# Motherboard_-_Rev2.net
KiCad netlist of a schematic drawn in EAGLE
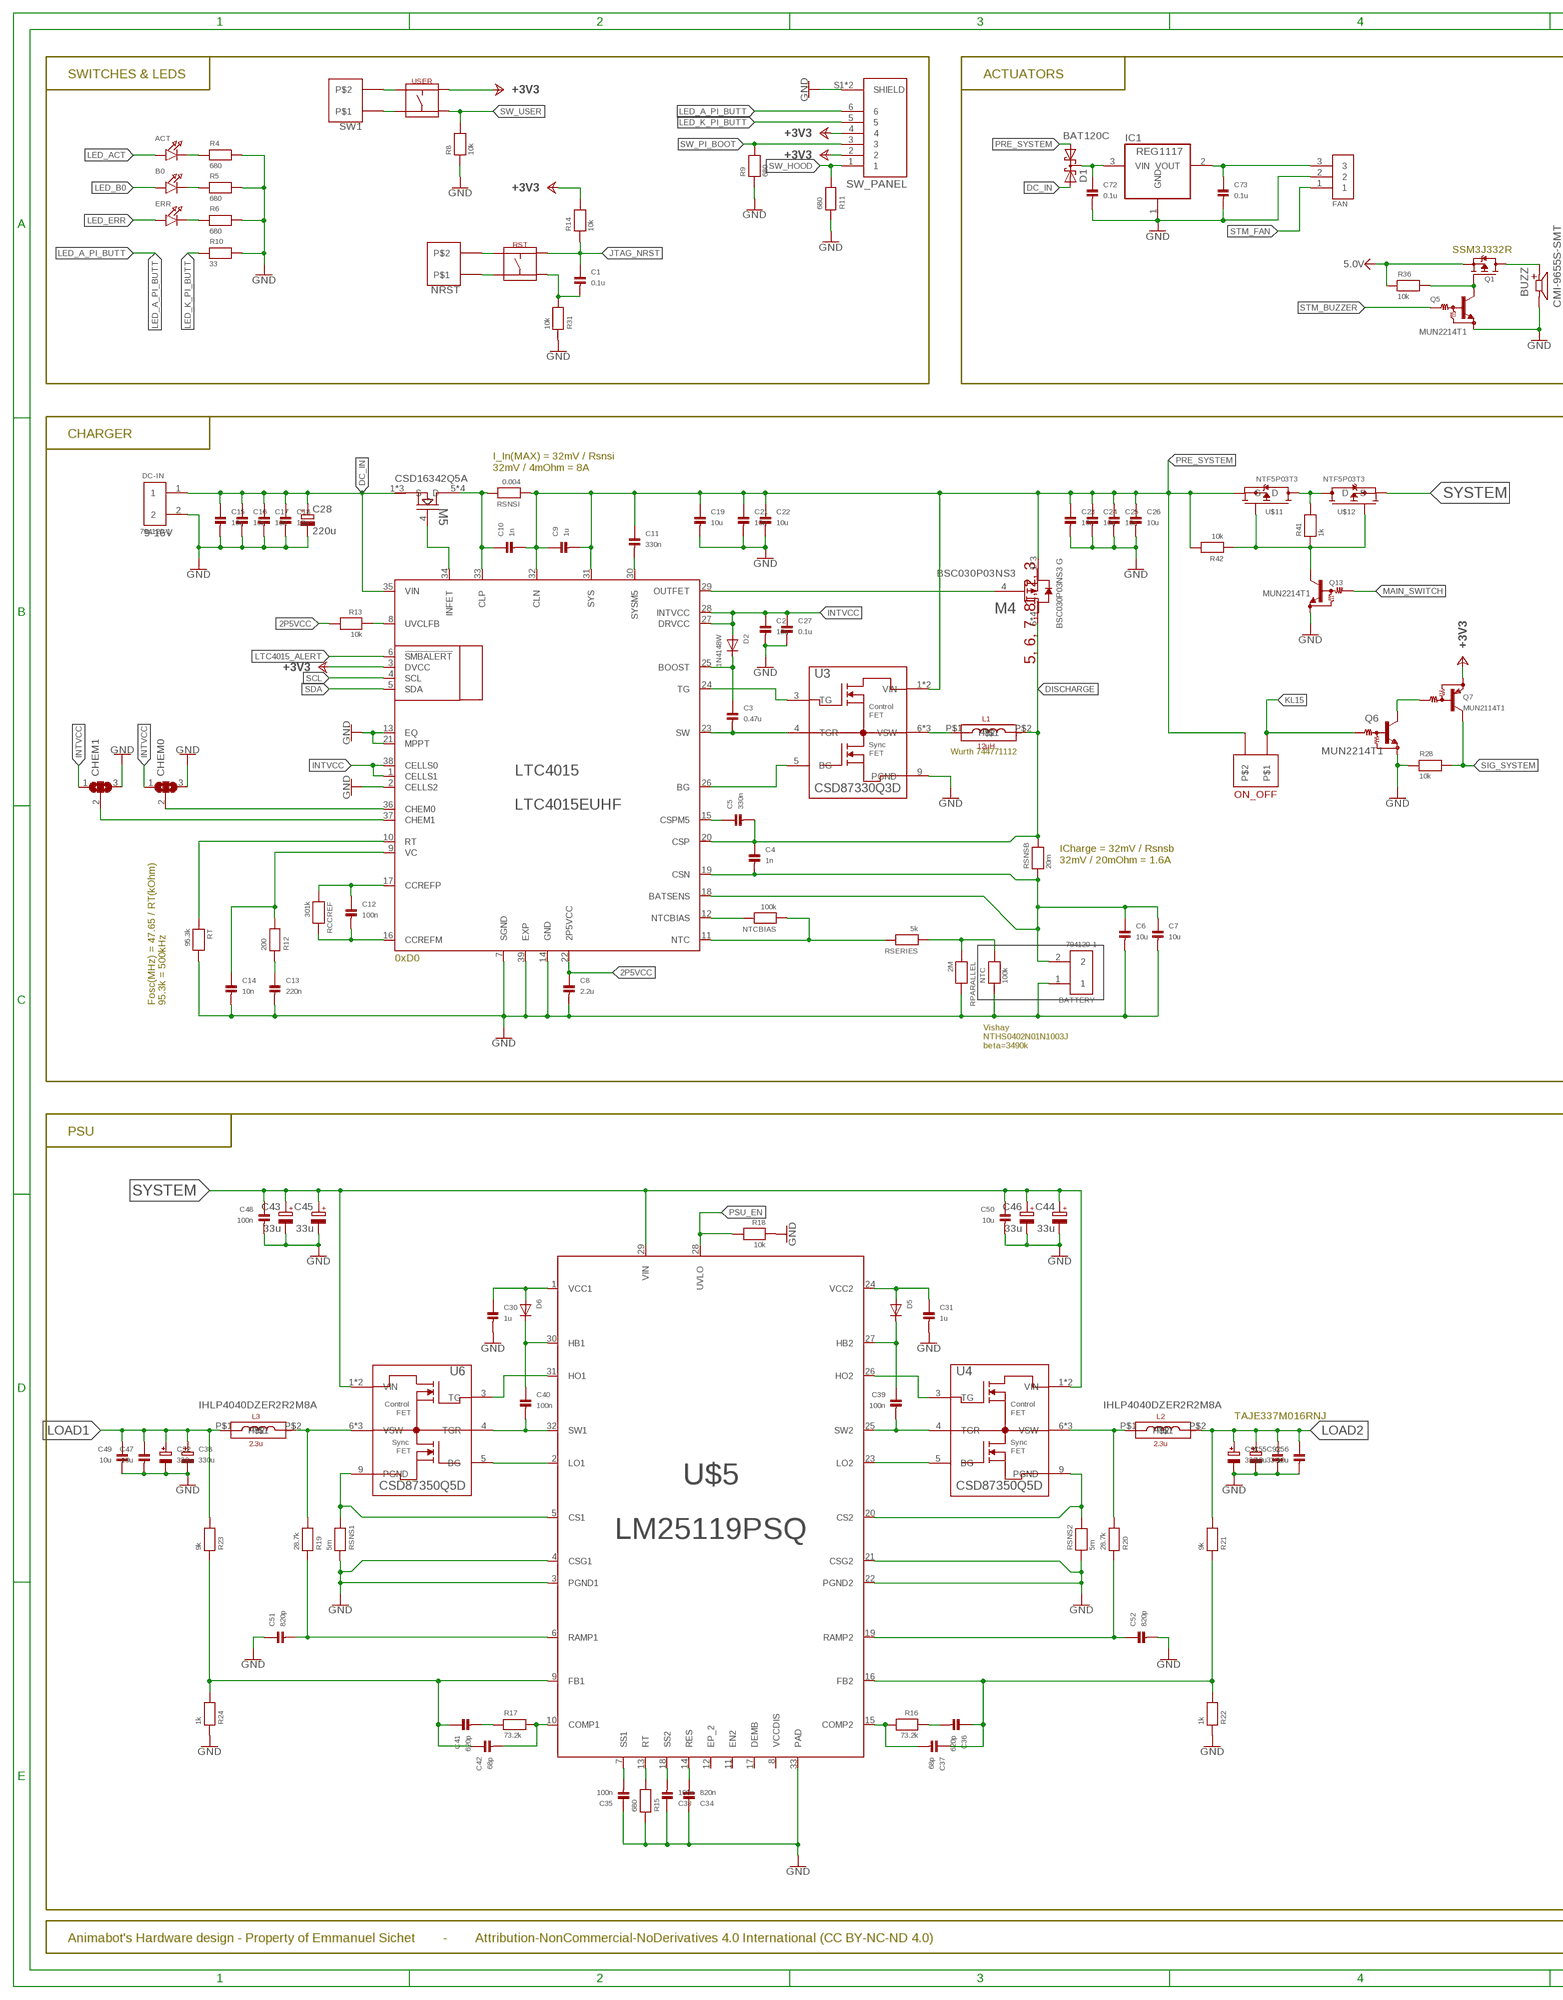
[diagram p0: schematic, sheet 1, part 1 of 2]
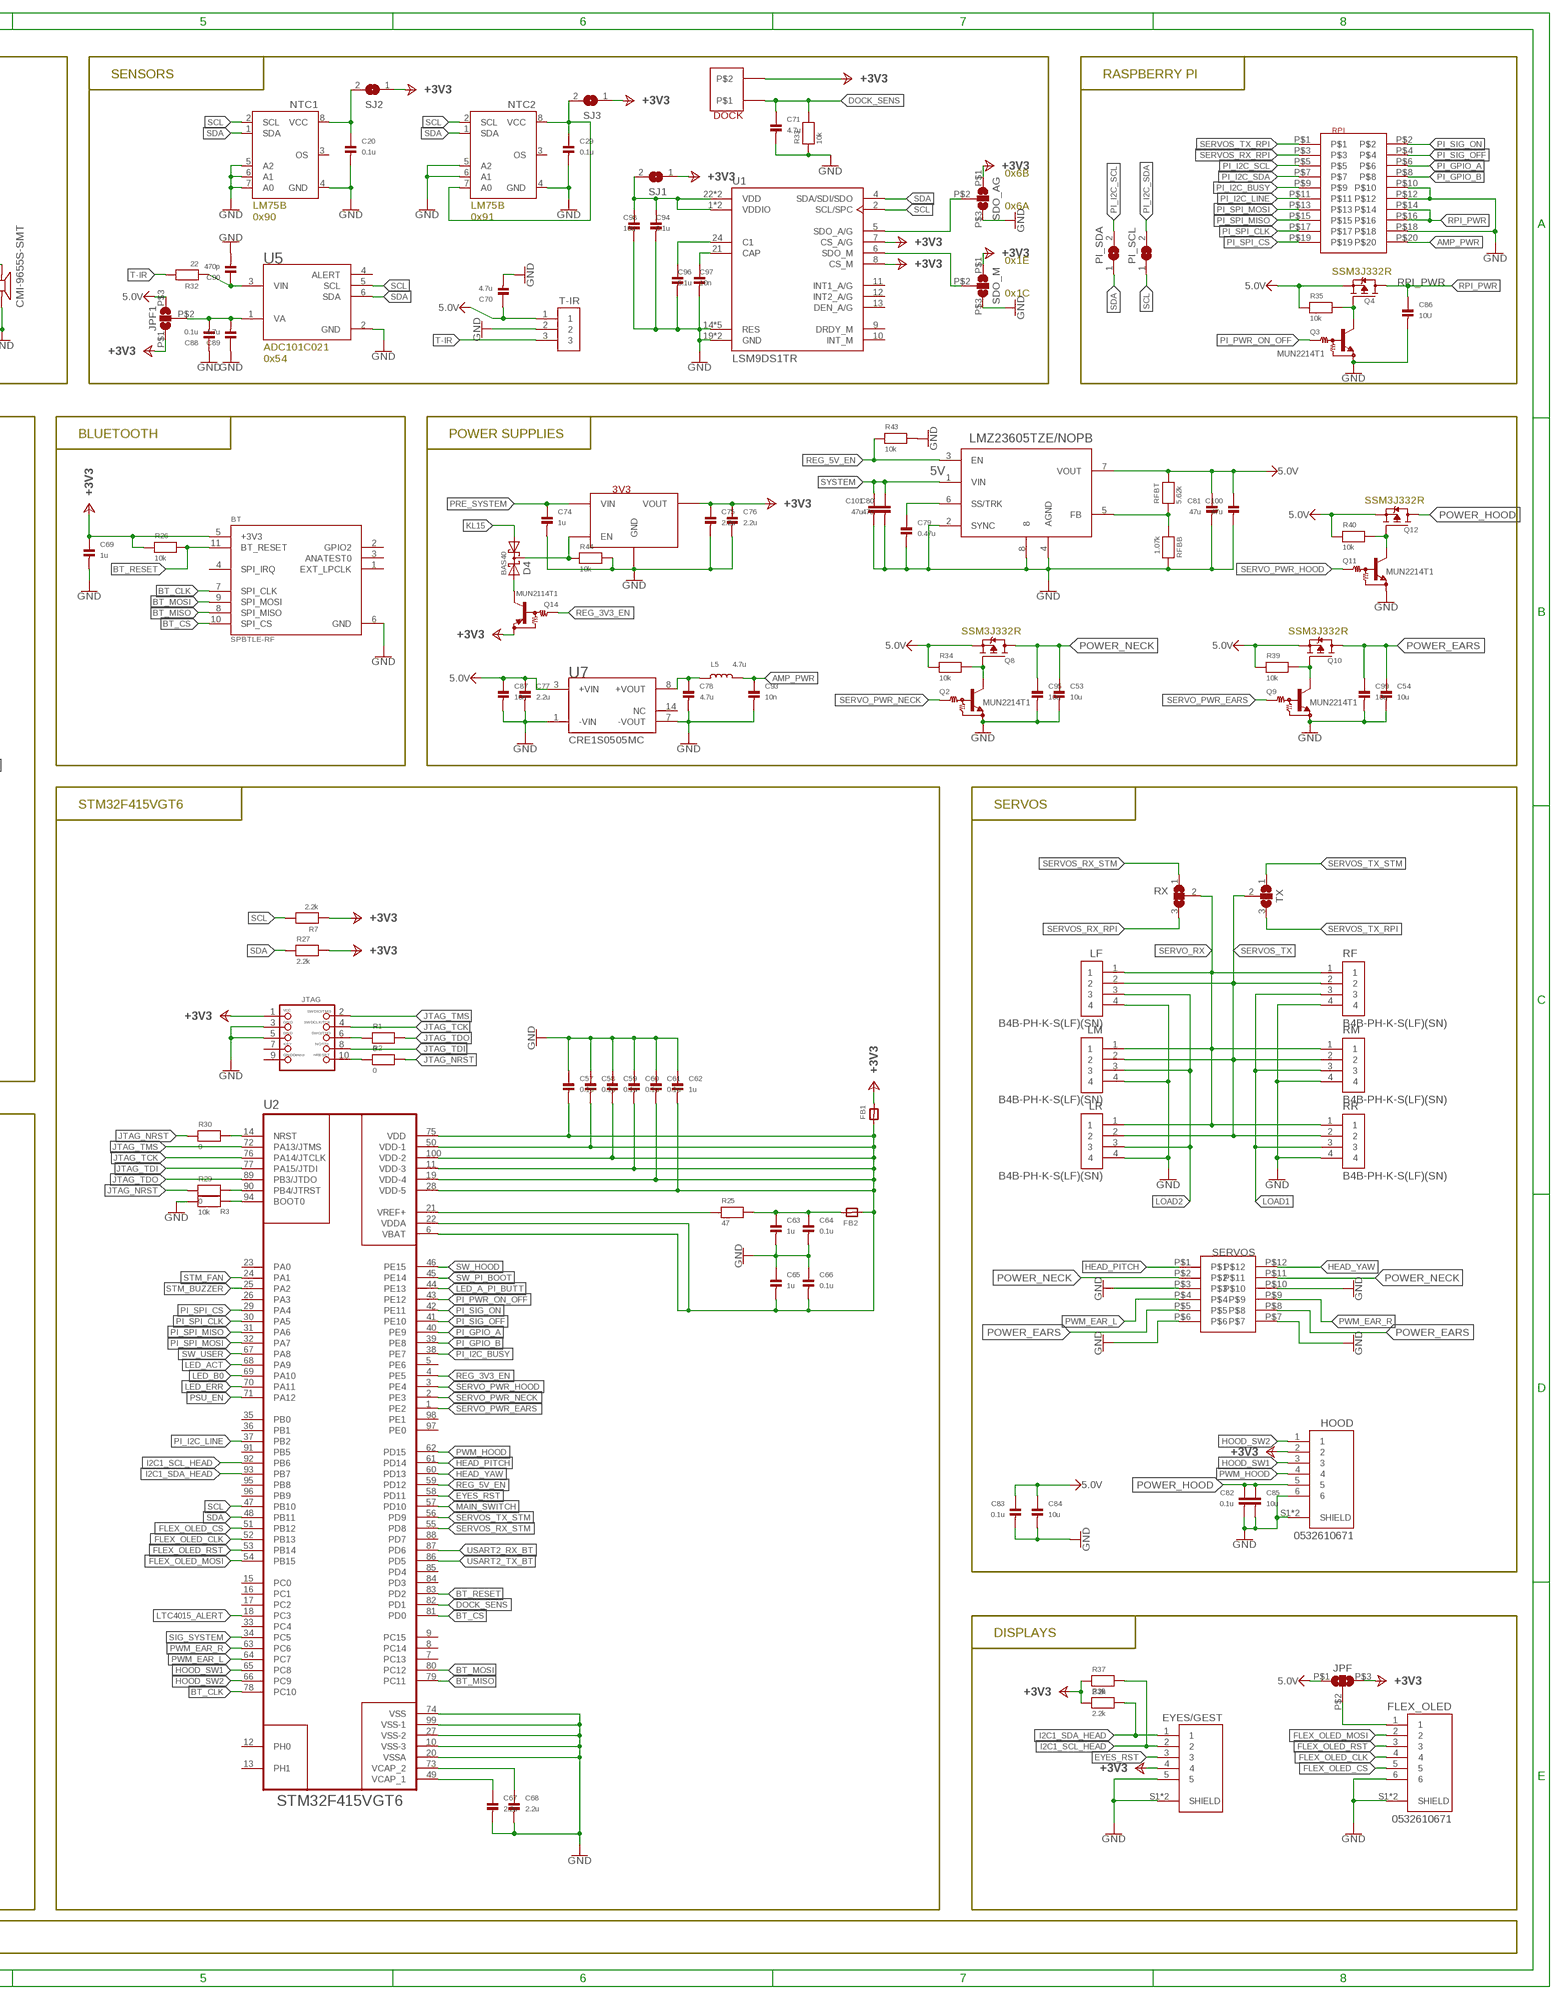
[diagram p1: schematic, sheet 1, part 2 of 2]

(export (version "E")
  (design (tool "Eeschema 10.0.6"))
  (components
    (comp (ref "3V3")
      (value "NCP5500DT-33.50-RKG")
      (footprint "eagle-import:NCP5500DT-33.50-RKG")
      (libsource (lib "eagle-import") (part "NCP5500DT-33.50-RKG"))
    )
    (comp (ref "5V")
      (value "LMZ23605TZE/NOPB")
      (footprint "eagle-import:TZA07A")
      (fields (field (name "MANUFACTURER_PART_NUMBER") "LMZ23605TZENOPB"))
      (libsource (lib "eagle-import") (part "LMZ23605TZE/NOPB"))
    )
    (comp (ref "ACT")
      (value "LED0805")
      (footprint "eagle-import:CHIPLED_0805")
      (libsource (lib "eagle-import") (part "LED0805"))
    )
    (comp (ref "B0")
      (value "LED0805")
      (footprint "eagle-import:CHIPLED_0805")
      (libsource (lib "eagle-import") (part "LED0805"))
    )
    (comp (ref "BATTERY")
      (value "794120-1")
      (footprint "eagle-import:TE_794120-1")
      (fields (field (name "MF") "TE Connectivity"))
      (libsource (lib "eagle-import") (part "794120-1"))
    )
    (comp (ref "BT")
      (value "SPBTLE-RF")
      (footprint "eagle-import:XCVR_SPBTLE-RF")
      (fields (field (name "MF") "STMicroelectronics"))
      (libsource (lib "eagle-import") (part "SPBTLE-RF"))
    )
    (comp (ref "BUZZ")
      (value "CMI-9655S-SMT")
      (footprint "eagle-import:CUI_CMI-9655S-SMT")
      (fields (field (name "MANUFACTURER") "CUI INC"))
      (libsource (lib "eagle-import") (part "CMI-9655S-SMT"))
    )
    (comp (ref "C1")
      (value "0.1u")
      (footprint "eagle-import:0805")
      (libsource (lib "eagle-import") (part "CAP_CERAMIC0805"))
    )
    (comp (ref "C2")
      (value "10u")
      (footprint "eagle-import:0805")
      (libsource (lib "eagle-import") (part "CAP_CERAMIC0805"))
    )
    (comp (ref "C3")
      (value "0.47u")
      (footprint "eagle-import:0805")
      (libsource (lib "eagle-import") (part "CAP_CERAMIC0805"))
    )
    (comp (ref "C4")
      (value "1n")
      (footprint "eagle-import:0805")
      (libsource (lib "eagle-import") (part "CAP_CERAMIC0805"))
    )
    (comp (ref "C5")
      (value "330n")
      (footprint "eagle-import:0805")
      (libsource (lib "eagle-import") (part "CAP_CERAMIC0805"))
    )
    (comp (ref "C6")
      (value "10u")
      (footprint "eagle-import:1206")
      (libsource (lib "eagle-import") (part "CAP_CERAMIC1206"))
    )
    (comp (ref "C7")
      (value "10u")
      (footprint "eagle-import:1206")
      (libsource (lib "eagle-import") (part "CAP_CERAMIC1206"))
    )
    (comp (ref "C8")
      (value "2.2u")
      (footprint "eagle-import:0805")
      (libsource (lib "eagle-import") (part "CAP_CERAMIC0805"))
    )
    (comp (ref "C9")
      (value "1u")
      (footprint "eagle-import:0805")
      (libsource (lib "eagle-import") (part "CAP_CERAMIC0805"))
    )
    (comp (ref "C10")
      (value "1n")
      (footprint "eagle-import:0805")
      (libsource (lib "eagle-import") (part "CAP_CERAMIC0805"))
    )
    (comp (ref "C11")
      (value "330n")
      (footprint "eagle-import:0805")
      (libsource (lib "eagle-import") (part "CAP_CERAMIC0805"))
    )
    (comp (ref "C12")
      (value "100n")
      (footprint "eagle-import:0805")
      (libsource (lib "eagle-import") (part "CAP_CERAMIC0805"))
    )
    (comp (ref "C13")
      (value "220n")
      (footprint "eagle-import:0805")
      (libsource (lib "eagle-import") (part "CAP_CERAMIC0805"))
    )
    (comp (ref "C14")
      (value "10n")
      (footprint "eagle-import:0805")
      (libsource (lib "eagle-import") (part "CAP_CERAMIC0805"))
    )
    (comp (ref "C15")
      (value "10u")
      (footprint "eagle-import:1206")
      (libsource (lib "eagle-import") (part "CAP_CERAMIC1206"))
    )
    (comp (ref "C16")
      (value "10u")
      (footprint "eagle-import:1206")
      (libsource (lib "eagle-import") (part "CAP_CERAMIC1206"))
    )
    (comp (ref "C17")
      (value "10u")
      (footprint "eagle-import:1206")
      (libsource (lib "eagle-import") (part "CAP_CERAMIC1206"))
    )
    (comp (ref "C18")
      (value "10u")
      (footprint "eagle-import:1206")
      (libsource (lib "eagle-import") (part "CAP_CERAMIC1206"))
    )
    (comp (ref "C19")
      (value "10u")
      (footprint "eagle-import:1206")
      (libsource (lib "eagle-import") (part "CAP_CERAMIC1206"))
    )
    (comp (ref "C20")
      (value "0.1u")
      (footprint "eagle-import:0805")
      (libsource (lib "eagle-import") (part "CAP_CERAMIC0805"))
    )
    (comp (ref "C21")
      (value "10u")
      (footprint "eagle-import:1206")
      (libsource (lib "eagle-import") (part "CAP_CERAMIC1206"))
    )
    (comp (ref "C22")
      (value "10u")
      (footprint "eagle-import:1206")
      (libsource (lib "eagle-import") (part "CAP_CERAMIC1206"))
    )
    (comp (ref "C23")
      (value "10u")
      (footprint "eagle-import:1206")
      (libsource (lib "eagle-import") (part "CAP_CERAMIC1206"))
    )
    (comp (ref "C24")
      (value "10u")
      (footprint "eagle-import:1206")
      (libsource (lib "eagle-import") (part "CAP_CERAMIC1206"))
    )
    (comp (ref "C25")
      (value "10u")
      (footprint "eagle-import:1206")
      (libsource (lib "eagle-import") (part "CAP_CERAMIC1206"))
    )
    (comp (ref "C26")
      (value "10u")
      (footprint "eagle-import:1206")
      (libsource (lib "eagle-import") (part "CAP_CERAMIC1206"))
    )
    (comp (ref "C27")
      (value "0.1u")
      (footprint "eagle-import:0805")
      (libsource (lib "eagle-import") (part "CAP_CERAMIC0805"))
    )
    (comp (ref "C28")
      (value "220u")
      (footprint "eagle-import:UD-10X10_NICHICON")
      (libsource (lib "eagle-import") (part "CPOL-EUUD-10X10"))
    )
    (comp (ref "C29")
      (value "0.1u")
      (footprint "eagle-import:0805")
      (libsource (lib "eagle-import") (part "CAP_CERAMIC0805"))
    )
    (comp (ref "C30")
      (value "1u")
      (footprint "eagle-import:0805")
      (libsource (lib "eagle-import") (part "CAP_CERAMIC0805"))
    )
    (comp (ref "C31")
      (value "1u")
      (footprint "eagle-import:0805")
      (libsource (lib "eagle-import") (part "CAP_CERAMIC0805"))
    )
    (comp (ref "C32")
      (value "330u")
      (footprint "eagle-import:EIA7343-31_D-R")
      (libsource (lib "eagle-import") (part "CAP_TANTALUMD/7343_REFLOW"))
    )
    (comp (ref "C33")
      (value "100n")
      (footprint "eagle-import:0805")
      (libsource (lib "eagle-import") (part "CAP_CERAMIC0805"))
    )
    (comp (ref "C34")
      (value "820n")
      (footprint "eagle-import:0805")
      (libsource (lib "eagle-import") (part "CAP_CERAMIC0805"))
    )
    (comp (ref "C35")
      (value "100n")
      (footprint "eagle-import:0805")
      (libsource (lib "eagle-import") (part "CAP_CERAMIC0805"))
    )
    (comp (ref "C36")
      (value "620p")
      (footprint "eagle-import:0805")
      (libsource (lib "eagle-import") (part "CAP_CERAMIC0805"))
    )
    (comp (ref "C37")
      (value "68p")
      (footprint "eagle-import:0805")
      (libsource (lib "eagle-import") (part "CAP_CERAMIC0805"))
    )
    (comp (ref "C38")
      (value "330u")
      (footprint "eagle-import:EIA7343-31_D-R")
      (libsource (lib "eagle-import") (part "CAP_TANTALUMD/7343_REFLOW"))
    )
    (comp (ref "C39")
      (value "100n")
      (footprint "eagle-import:0805")
      (libsource (lib "eagle-import") (part "CAP_CERAMIC0805"))
    )
    (comp (ref "C40")
      (value "100n")
      (footprint "eagle-import:0805")
      (libsource (lib "eagle-import") (part "CAP_CERAMIC0805"))
    )
    (comp (ref "C41")
      (value "620p")
      (footprint "eagle-import:0805")
      (libsource (lib "eagle-import") (part "CAP_CERAMIC0805"))
    )
    (comp (ref "C42")
      (value "68p")
      (footprint "eagle-import:0805")
      (libsource (lib "eagle-import") (part "CAP_CERAMIC0805"))
    )
    (comp (ref "C43")
      (value "33u")
      (footprint "eagle-import:UD-6,3X7,7_NICHICON")
      (libsource (lib "eagle-import") (part "CPOL-EUUD-6,3X7,7"))
    )
    (comp (ref "C44")
      (value "33u")
      (footprint "eagle-import:UD-6,3X7,7_NICHICON")
      (libsource (lib "eagle-import") (part "CPOL-EUUD-6,3X7,7"))
    )
    (comp (ref "C45")
      (value "33u")
      (footprint "eagle-import:UD-6,3X7,7_NICHICON")
      (libsource (lib "eagle-import") (part "CPOL-EUUD-6,3X7,7"))
    )
    (comp (ref "C46")
      (value "33u")
      (footprint "eagle-import:UD-6,3X7,7_NICHICON")
      (libsource (lib "eagle-import") (part "CPOL-EUUD-6,3X7,7"))
    )
    (comp (ref "C47")
      (value "10u")
      (footprint "eagle-import:1206")
      (libsource (lib "eagle-import") (part "CAP_CERAMIC1206"))
    )
    (comp (ref "C48")
      (value "100n")
      (footprint "eagle-import:1206")
      (libsource (lib "eagle-import") (part "CAP_CERAMIC1206"))
    )
    (comp (ref "C49")
      (value "10u")
      (footprint "eagle-import:1206")
      (libsource (lib "eagle-import") (part "CAP_CERAMIC1206"))
    )
    (comp (ref "C50")
      (value "10u")
      (footprint "eagle-import:1206")
      (libsource (lib "eagle-import") (part "CAP_CERAMIC1206"))
    )
    (comp (ref "C51")
      (value "820p")
      (footprint "eagle-import:0805")
      (libsource (lib "eagle-import") (part "CAP_CERAMIC0805"))
    )
    (comp (ref "C52")
      (value "820p")
      (footprint "eagle-import:0805")
      (libsource (lib "eagle-import") (part "CAP_CERAMIC0805"))
    )
    (comp (ref "C53")
      (value "10u")
      (footprint "eagle-import:1206")
      (libsource (lib "eagle-import") (part "CAP_CERAMIC1206"))
    )
    (comp (ref "C54")
      (value "10u")
      (footprint "eagle-import:1206")
      (libsource (lib "eagle-import") (part "CAP_CERAMIC1206"))
    )
    (comp (ref "C55")
      (value "10u")
      (footprint "eagle-import:1206")
      (libsource (lib "eagle-import") (part "CAP_CERAMIC1206"))
    )
    (comp (ref "C56")
      (value "10u")
      (footprint "eagle-import:1206")
      (libsource (lib "eagle-import") (part "CAP_CERAMIC1206"))
    )
    (comp (ref "C57")
      (value "0.1u")
      (footprint "eagle-import:0805")
      (libsource (lib "eagle-import") (part "CAP_CERAMIC0805"))
    )
    (comp (ref "C58")
      (value "0.1u")
      (footprint "eagle-import:0805")
      (libsource (lib "eagle-import") (part "CAP_CERAMIC0805"))
    )
    (comp (ref "C59")
      (value "0.1u")
      (footprint "eagle-import:0805")
      (libsource (lib "eagle-import") (part "CAP_CERAMIC0805"))
    )
    (comp (ref "C60")
      (value "0.1u")
      (footprint "eagle-import:0805")
      (libsource (lib "eagle-import") (part "CAP_CERAMIC0805"))
    )
    (comp (ref "C61")
      (value "0.1u")
      (footprint "eagle-import:0805")
      (libsource (lib "eagle-import") (part "CAP_CERAMIC0805"))
    )
    (comp (ref "C62")
      (value "1u")
      (footprint "eagle-import:0805")
      (libsource (lib "eagle-import") (part "CAP_CERAMIC0805"))
    )
    (comp (ref "C63")
      (value "1u")
      (footprint "eagle-import:0805")
      (libsource (lib "eagle-import") (part "CAP_CERAMIC0805"))
    )
    (comp (ref "C64")
      (value "0.1u")
      (footprint "eagle-import:0805")
      (libsource (lib "eagle-import") (part "CAP_CERAMIC0805"))
    )
    (comp (ref "C65")
      (value "1u")
      (footprint "eagle-import:0805")
      (libsource (lib "eagle-import") (part "CAP_CERAMIC0805"))
    )
    (comp (ref "C66")
      (value "0.1u")
      (footprint "eagle-import:0805")
      (libsource (lib "eagle-import") (part "CAP_CERAMIC0805"))
    )
    (comp (ref "C67")
      (value "2.2u")
      (footprint "eagle-import:0805")
      (libsource (lib "eagle-import") (part "CAP_CERAMIC0805"))
    )
    (comp (ref "C68")
      (value "2.2u")
      (footprint "eagle-import:0805")
      (libsource (lib "eagle-import") (part "CAP_CERAMIC0805"))
    )
    (comp (ref "C69")
      (value "1u")
      (footprint "eagle-import:0805")
      (libsource (lib "eagle-import") (part "CAP_CERAMIC0805"))
    )
    (comp (ref "C70")
      (value "4.7u")
      (footprint "eagle-import:0805")
      (libsource (lib "eagle-import") (part "CAP_CERAMIC0805"))
    )
    (comp (ref "C71")
      (value "4.7u")
      (footprint "eagle-import:0805")
      (libsource (lib "eagle-import") (part "CAP_CERAMIC0805"))
    )
    (comp (ref "C72")
      (value "0.1u")
      (footprint "eagle-import:0805")
      (libsource (lib "eagle-import") (part "CAP_CERAMIC0805"))
    )
    (comp (ref "C73")
      (value "0.1u")
      (footprint "eagle-import:0805")
      (libsource (lib "eagle-import") (part "CAP_CERAMIC0805"))
    )
    (comp (ref "C74")
      (value "1u")
      (footprint "eagle-import:0805")
      (libsource (lib "eagle-import") (part "CAP_CERAMIC0805"))
    )
    (comp (ref "C75")
      (value "2.2u")
      (footprint "eagle-import:0805")
      (libsource (lib "eagle-import") (part "CAP_CERAMIC0805"))
    )
    (comp (ref "C76")
      (value "2.2u")
      (footprint "eagle-import:0805")
      (libsource (lib "eagle-import") (part "CAP_CERAMIC0805"))
    )
    (comp (ref "C77")
      (value "2.2u")
      (footprint "eagle-import:0805")
      (libsource (lib "eagle-import") (part "CAP_CERAMIC0805"))
    )
    (comp (ref "C78")
      (value "4.7u")
      (footprint "eagle-import:0805")
      (libsource (lib "eagle-import") (part "CAP_CERAMIC0805"))
    )
    (comp (ref "C79")
      (value "0.47u")
      (footprint "eagle-import:0805")
      (libsource (lib "eagle-import") (part "CAP_CERAMIC0805"))
    )
    (comp (ref "C80")
      (value "47u")
      (footprint "eagle-import:1206")
      (libsource (lib "eagle-import") (part "CAP_CERAMIC1206"))
    )
    (comp (ref "C81")
      (value "47u")
      (footprint "eagle-import:1206")
      (libsource (lib "eagle-import") (part "CAP_CERAMIC1206"))
    )
    (comp (ref "C82")
      (value "0.1u")
      (footprint "eagle-import:0805")
      (libsource (lib "eagle-import") (part "CAP_CERAMIC0805"))
    )
    (comp (ref "C83")
      (value "0.1u")
      (footprint "eagle-import:0805")
      (libsource (lib "eagle-import") (part "CAP_CERAMIC0805"))
    )
    (comp (ref "C84")
      (value "10u")
      (footprint "eagle-import:1206")
      (libsource (lib "eagle-import") (part "CAP_CERAMIC1206"))
    )
    (comp (ref "C85")
      (value "10u")
      (footprint "eagle-import:1206")
      (libsource (lib "eagle-import") (part "CAP_CERAMIC1206"))
    )
    (comp (ref "C86")
      (value "10U")
      (footprint "eagle-import:0805")
      (libsource (lib "eagle-import") (part "CAP_CERAMIC0805"))
    )
    (comp (ref "C87")
      (value "10n")
      (footprint "eagle-import:0805")
      (libsource (lib "eagle-import") (part "CAP_CERAMIC0805"))
    )
    (comp (ref "C88")
      (value "0.1u")
      (footprint "eagle-import:0805")
      (libsource (lib "eagle-import") (part "CAP_CERAMIC0805"))
    )
    (comp (ref "C89")
      (value "4.7u")
      (footprint "eagle-import:0805")
      (libsource (lib "eagle-import") (part "CAP_CERAMIC0805"))
    )
    (comp (ref "C90")
      (value "470p")
      (footprint "eagle-import:0805")
      (libsource (lib "eagle-import") (part "CAP_CERAMIC0805"))
    )
    (comp (ref "C91")
      (value "330u")
      (footprint "eagle-import:EIA7343-31_D-R")
      (libsource (lib "eagle-import") (part "CAP_TANTALUMD/7343_REFLOW"))
    )
    (comp (ref "C92")
      (value "330u")
      (footprint "eagle-import:EIA7343-31_D-R")
      (libsource (lib "eagle-import") (part "CAP_TANTALUMD/7343_REFLOW"))
    )
    (comp (ref "C93")
      (value "10n")
      (footprint "eagle-import:0805")
      (libsource (lib "eagle-import") (part "CAP_CERAMIC0805"))
    )
    (comp (ref "C94")
      (value "0.1u")
      (footprint "eagle-import:0805")
      (libsource (lib "eagle-import") (part "CAP_CERAMIC0805"))
    )
    (comp (ref "C95")
      (value "10u")
      (footprint "eagle-import:1206")
      (libsource (lib "eagle-import") (part "CAP_CERAMIC1206"))
    )
    (comp (ref "C96")
      (value "0.1u")
      (footprint "eagle-import:0805")
      (libsource (lib "eagle-import") (part "CAP_CERAMIC0805"))
    )
    (comp (ref "C97")
      (value "10n")
      (footprint "eagle-import:0805")
      (libsource (lib "eagle-import") (part "CAP_CERAMIC0805"))
    )
    (comp (ref "C98")
      (value "10u")
      (footprint "eagle-import:0805")
      (libsource (lib "eagle-import") (part "CAP_CERAMIC0805"))
    )
    (comp (ref "C99")
      (value "10u")
      (footprint "eagle-import:1206")
      (libsource (lib "eagle-import") (part "CAP_CERAMIC1206"))
    )
    (comp (ref "C100")
      (value "47u")
      (footprint "eagle-import:1206")
      (libsource (lib "eagle-import") (part "CAP_CERAMIC1206"))
    )
    (comp (ref "C101")
      (value "47u")
      (footprint "eagle-import:1206")
      (libsource (lib "eagle-import") (part "CAP_CERAMIC1206"))
    )
    (comp (ref "CHEM0")
      (value "SJ2W")
      (footprint "eagle-import:SJ_2")
      (libsource (lib "eagle-import") (part "SJ2W"))
    )
    (comp (ref "CHEM1")
      (value "SJ2W")
      (footprint "eagle-import:SJ_2")
      (libsource (lib "eagle-import") (part "SJ2W"))
    )
    (comp (ref "D1")
      (value "BAT120C")
      (footprint "eagle-import:SOT223")
      (libsource (lib "eagle-import") (part "BAT120C"))
    )
    (comp (ref "D2")
      (value "1N4148W")
      (footprint "eagle-import:SOD-123")
      (libsource (lib "eagle-import") (part "DIODESOD-123"))
    )
    (comp (ref "D4")
      (value "BAS40")
      (footprint "eagle-import:SOT23")
      (libsource (lib "eagle-import") (part "BAS40-05"))
    )
    (comp (ref "D5")
      (value "DIODESOD-123")
      (footprint "eagle-import:SOD-123")
      (libsource (lib "eagle-import") (part "DIODESOD-123"))
    )
    (comp (ref "D6")
      (value "DIODESOD-123")
      (footprint "eagle-import:SOD-123")
      (libsource (lib "eagle-import") (part "DIODESOD-123"))
    )
    (comp (ref "DC-IN")
      (value "794120-1")
      (footprint "eagle-import:TE_794120-1")
      (fields (field (name "MF") "TE Connectivity"))
      (libsource (lib "eagle-import") (part "794120-1"))
    )
    (comp (ref "DOCK")
      (value "MOLEX_53398")
      (footprint "eagle-import:MOLEX_53398")
      (libsource (lib "eagle-import") (part "MOLEX_53398"))
    )
    (comp (ref "ERR")
      (value "LED0805")
      (footprint "eagle-import:CHIPLED_0805")
      (libsource (lib "eagle-import") (part "LED0805"))
    )
    (comp (ref "EYES/GEST")
      (value "0532610571")
      (footprint "eagle-import:MOLEX_0532610571")
      (fields (field (name "MF") "Molex, LLC"))
      (libsource (lib "eagle-import") (part "0532610571"))
    )
    (comp (ref "FAN")
      (value "0532610371")
      (footprint "eagle-import:MOLEX_0532610371")
      (fields (field (name "MF") "Molex, LLC"))
      (libsource (lib "eagle-import") (part "0532610371"))
    )
    (comp (ref "FB1")
      (value "FERRITE_0805")
      (footprint "eagle-import:_0805")
      (libsource (lib "eagle-import") (part "FERRITE_0805"))
    )
    (comp (ref "FB2")
      (value "FERRITE_0805")
      (footprint "eagle-import:_0805")
      (libsource (lib "eagle-import") (part "FERRITE_0805"))
    )
    (comp (ref "FLEX_OLED")
      (value "0532610671")
      (footprint "eagle-import:MOLEX_0532610671")
      (fields (field (name "MF") "Molex, LLC"))
      (libsource (lib "eagle-import") (part "0532610671"))
    )
    (comp (ref "HOOD")
      (value "0532610671")
      (footprint "eagle-import:MOLEX_0532610671")
      (fields (field (name "MF") "Molex, LLC"))
      (libsource (lib "eagle-import") (part "0532610671"))
    )
    (comp (ref "IC1")
      (value "REG1117")
      (footprint "eagle-import:SOT223")
      (libsource (lib "eagle-import") (part "REG1117"))
    )
    (comp (ref "JPF")
      (value "SJ2WSJ_3")
      (footprint "eagle-import:SJ_3")
      (libsource (lib "eagle-import") (part "SJ2WSJ_3"))
    )
    (comp (ref "JPF1")
      (value "SJ2WSJ_3")
      (footprint "eagle-import:SJ_3")
      (libsource (lib "eagle-import") (part "SJ2WSJ_3"))
    )
    (comp (ref "JTAG")
      (value "JTAG-CORTEXM3")
      (footprint "eagle-import:2X05_1.27MM_SMT")
      (libsource (lib "eagle-import") (part "JTAG-CORTEXM3"))
    )
    (comp (ref "L1")
      (value "12µH")
      (footprint "eagle-import:SRR1210-680MTR")
      (libsource (lib "eagle-import") (part "SRR1210-680MTR"))
    )
    (comp (ref "L2")
      (value "2.3u")
      (footprint "eagle-import:SRR1210-680MTR")
      (libsource (lib "eagle-import") (part "SRR1210-680MTR"))
    )
    (comp (ref "L3")
      (value "2.3u")
      (footprint "eagle-import:SRR1210-680MTR")
      (libsource (lib "eagle-import") (part "SRR1210-680MTR"))
    )
    (comp (ref "L5")
      (value "4.7u")
      (footprint "eagle-import:0805")
      (libsource (lib "eagle-import") (part "INDUCTOR0805"))
    )
    (comp (ref "LF")
      (value "B4B-PH-K-S(LF)(SN)")
      (footprint "eagle-import:JST_B4B-PH-K-S(LF)(SN)")
      (fields (field (name "MF") "JST Sales") (field (name "MP") "B4B-PH-K-S_LF__SN_"))
      (libsource (lib "eagle-import") (part "B4B-PH-K-S(LF)(SN)"))
    )
    (comp (ref "LM")
      (value "B4B-PH-K-S(LF)(SN)")
      (footprint "eagle-import:JST_B4B-PH-K-S(LF)(SN)")
      (fields (field (name "MF") "JST Sales") (field (name "MP") "B4B-PH-K-S_LF__SN_"))
      (libsource (lib "eagle-import") (part "B4B-PH-K-S(LF)(SN)"))
    )
    (comp (ref "LR")
      (value "B4B-PH-K-S(LF)(SN)")
      (footprint "eagle-import:JST_B4B-PH-K-S(LF)(SN)")
      (fields (field (name "MF") "JST Sales") (field (name "MP") "B4B-PH-K-S_LF__SN_"))
      (libsource (lib "eagle-import") (part "B4B-PH-K-S(LF)(SN)"))
    )
    (comp (ref "LTC4015")
      (value "LTC4015EUHF")
      (footprint "eagle-import:QFN50P700X500X80-39N")
      (fields (field (name "MF") "Linear Technology/Analog") (field (name "MP") "LTC4015EUHF#PBF"))
      (libsource (lib "eagle-import") (part "LTC4015EUHF#PBF"))
    )
    (comp (ref "M4")
      (value "INFINEON_BSC030P03NS3_GINFINEON_BSC030P03NS3_G_0_0")
      (footprint "eagle-import:INFINEON_BSC030P03NS3_G_0")
      (fields (field (name "MF") "Infineon") (field (name "MPN") "BSC030P03NS3 G"))
      (libsource (lib "eagle-import") (part "INFINEON_BSC030P03NS3_GINFINEON_BSC030P03NS3_G_0_0"))
    )
    (comp (ref "M5")
      (value "CSD16342Q5A-REV2")
      (footprint "eagle-import:DQJ8")
      (libsource (lib "eagle-import") (part "CSD16342Q5A-REV2"))
    )
    (comp (ref "NRST")
      (value "MOLEX_53398")
      (footprint "eagle-import:MOLEX_53398")
      (libsource (lib "eagle-import") (part "MOLEX_53398"))
    )
    (comp (ref "NTC")
      (value "100k")
      (footprint "eagle-import:1206")
      (libsource (lib "eagle-import") (part "RESISTOR1206"))
    )
    (comp (ref "NTC1")
      (value "TEMP_LM75B")
      (footprint "eagle-import:TSSOP8")
      (libsource (lib "eagle-import") (part "TEMP_LM75B"))
    )
    (comp (ref "NTC2")
      (value "TEMP_LM75B")
      (footprint "eagle-import:TSSOP8")
      (libsource (lib "eagle-import") (part "TEMP_LM75B"))
    )
    (comp (ref "NTCBIAS")
      (value "100k")
      (footprint "eagle-import:0805")
      (libsource (lib "eagle-import") (part "RESISTOR0805"))
    )
    (comp (ref "ON_OFF")
      (value "MOLEX_53398")
      (footprint "eagle-import:MOLEX_53398")
      (libsource (lib "eagle-import") (part "MOLEX_53398"))
    )
    (comp (ref "PI_SCL")
      (value "SOLDERJUMPERREFLOW")
      (footprint "eagle-import:SOLDERJUMPER_REFLOW")
      (libsource (lib "eagle-import") (part "SOLDERJUMPERREFLOW"))
    )
    (comp (ref "PI_SDA")
      (value "SOLDERJUMPERREFLOW")
      (footprint "eagle-import:SOLDERJUMPER_REFLOW")
      (libsource (lib "eagle-import") (part "SOLDERJUMPERREFLOW"))
    )
    (comp (ref "Q1")
      (value "MOSFET-PWIDE")
      (footprint "eagle-import:SOT23-WIDE")
      (libsource (lib "eagle-import") (part "MOSFET-PWIDE"))
    )
    (comp (ref "Q2")
      (value "MUN2214T1")
      (footprint "eagle-import:SC59-BEC")
      (libsource (lib "eagle-import") (part "MUN2214T1"))
    )
    (comp (ref "Q3")
      (value "MUN2214T1")
      (footprint "eagle-import:SC59-BEC")
      (libsource (lib "eagle-import") (part "MUN2214T1"))
    )
    (comp (ref "Q4")
      (value "MOSFET-PWIDE")
      (footprint "eagle-import:SOT23-WIDE")
      (libsource (lib "eagle-import") (part "MOSFET-PWIDE"))
    )
    (comp (ref "Q5")
      (value "MUN2214T1")
      (footprint "eagle-import:SC59-BEC")
      (libsource (lib "eagle-import") (part "MUN2214T1"))
    )
    (comp (ref "Q6")
      (value "MUN2214T1")
      (footprint "eagle-import:SC59-BEC")
      (libsource (lib "eagle-import") (part "transistor-npn_398_MUN2214T1"))
    )
    (comp (ref "Q7")
      (value "MUN2114T1")
      (footprint "eagle-import:SC59-BEC")
      (libsource (lib "eagle-import") (part "MUN2114T1"))
    )
    (comp (ref "Q8")
      (value "MOSFET-PWIDE")
      (footprint "eagle-import:SOT23-WIDE")
      (libsource (lib "eagle-import") (part "MOSFET-PWIDE"))
    )
    (comp (ref "Q9")
      (value "MUN2214T1")
      (footprint "eagle-import:SC59-BEC")
      (libsource (lib "eagle-import") (part "MUN2214T1"))
    )
    (comp (ref "Q10")
      (value "MOSFET-PWIDE")
      (footprint "eagle-import:SOT23-WIDE")
      (libsource (lib "eagle-import") (part "MOSFET-PWIDE"))
    )
    (comp (ref "Q11")
      (value "MUN2214T1")
      (footprint "eagle-import:SC59-BEC")
      (libsource (lib "eagle-import") (part "MUN2214T1"))
    )
    (comp (ref "Q12")
      (value "MOSFET-PWIDE")
      (footprint "eagle-import:SOT23-WIDE")
      (libsource (lib "eagle-import") (part "MOSFET-PWIDE"))
    )
    (comp (ref "Q13")
      (value "MUN2214T1")
      (footprint "eagle-import:SC59-BEC")
      (libsource (lib "eagle-import") (part "MUN2214T1"))
    )
    (comp (ref "Q14")
      (value "MUN2114T1")
      (footprint "eagle-import:SC59-BEC")
      (libsource (lib "eagle-import") (part "MUN2114T1"))
    )
    (comp (ref "R1")
      (value "0")
      (footprint "eagle-import:0805")
      (libsource (lib "eagle-import") (part "RESISTOR0805"))
    )
    (comp (ref "R2")
      (value "0")
      (footprint "eagle-import:0805")
      (libsource (lib "eagle-import") (part "RESISTOR0805"))
    )
    (comp (ref "R3")
      (value "10k")
      (footprint "eagle-import:0805")
      (libsource (lib "eagle-import") (part "RESISTOR0805"))
    )
    (comp (ref "R4")
      (value "680")
      (footprint "eagle-import:0805")
      (libsource (lib "eagle-import") (part "RESISTOR0805"))
    )
    (comp (ref "R5")
      (value "680")
      (footprint "eagle-import:0805")
      (libsource (lib "eagle-import") (part "RESISTOR0805"))
    )
    (comp (ref "R6")
      (value "680")
      (footprint "eagle-import:0805")
      (libsource (lib "eagle-import") (part "RESISTOR0805"))
    )
    (comp (ref "R7")
      (value "2.2k")
      (footprint "eagle-import:0805")
      (libsource (lib "eagle-import") (part "RESISTOR0805"))
    )
    (comp (ref "R8")
      (value "10k")
      (footprint "eagle-import:0805")
      (libsource (lib "eagle-import") (part "RESISTOR0805"))
    )
    (comp (ref "R9")
      (value "680")
      (footprint "eagle-import:0805")
      (libsource (lib "eagle-import") (part "RESISTOR0805"))
    )
    (comp (ref "R10")
      (value "33")
      (footprint "eagle-import:0805")
      (libsource (lib "eagle-import") (part "RESISTOR0805"))
    )
    (comp (ref "R11")
      (value "680")
      (footprint "eagle-import:0805")
      (libsource (lib "eagle-import") (part "RESISTOR0805"))
    )
    (comp (ref "R12")
      (value "200")
      (footprint "eagle-import:0805")
      (libsource (lib "eagle-import") (part "RESISTOR0805"))
    )
    (comp (ref "R13")
      (value "10k")
      (footprint "eagle-import:0805")
      (libsource (lib "eagle-import") (part "RESISTOR0805"))
    )
    (comp (ref "R14")
      (value "10k")
      (footprint "eagle-import:0805")
      (libsource (lib "eagle-import") (part "RESISTOR0805"))
    )
    (comp (ref "R15")
      (value "680")
      (footprint "eagle-import:0805")
      (libsource (lib "eagle-import") (part "RESISTOR0805"))
    )
    (comp (ref "R16")
      (value "73.2k")
      (footprint "eagle-import:0805")
      (libsource (lib "eagle-import") (part "RESISTOR0805"))
    )
    (comp (ref "R17")
      (value "73.2k")
      (footprint "eagle-import:0805")
      (libsource (lib "eagle-import") (part "RESISTOR0805"))
    )
    (comp (ref "R18")
      (value "10k")
      (footprint "eagle-import:0805")
      (libsource (lib "eagle-import") (part "RESISTOR0805"))
    )
    (comp (ref "R19")
      (value "28.7k")
      (footprint "eagle-import:0805")
      (libsource (lib "eagle-import") (part "RESISTOR0805"))
    )
    (comp (ref "R20")
      (value "28.7k")
      (footprint "eagle-import:0805")
      (libsource (lib "eagle-import") (part "RESISTOR0805"))
    )
    (comp (ref "R21")
      (value "9k")
      (footprint "eagle-import:0805")
      (libsource (lib "eagle-import") (part "RESISTOR0805"))
    )
    (comp (ref "R22")
      (value "1k")
      (footprint "eagle-import:0805")
      (libsource (lib "eagle-import") (part "RESISTOR0805"))
    )
    (comp (ref "R23")
      (value "9k")
      (footprint "eagle-import:0805")
      (libsource (lib "eagle-import") (part "RESISTOR0805"))
    )
    (comp (ref "R24")
      (value "1k")
      (footprint "eagle-import:0805")
      (libsource (lib "eagle-import") (part "RESISTOR0805"))
    )
    (comp (ref "R25")
      (value "47")
      (footprint "eagle-import:0805")
      (libsource (lib "eagle-import") (part "RESISTOR0805"))
    )
    (comp (ref "R26")
      (value "10k")
      (footprint "eagle-import:0805")
      (libsource (lib "eagle-import") (part "RESISTOR0805"))
    )
    (comp (ref "R27")
      (value "2.2k")
      (footprint "eagle-import:0805")
      (libsource (lib "eagle-import") (part "RESISTOR0805"))
    )
    (comp (ref "R28")
      (value "10k")
      (footprint "eagle-import:0805")
      (libsource (lib "eagle-import") (part "RESISTOR0805"))
    )
    (comp (ref "R29")
      (value "0")
      (footprint "eagle-import:0805")
      (libsource (lib "eagle-import") (part "RESISTOR0805"))
    )
    (comp (ref "R30")
      (value "0")
      (footprint "eagle-import:0805")
      (libsource (lib "eagle-import") (part "RESISTOR0805"))
    )
    (comp (ref "R31")
      (value "10k")
      (footprint "eagle-import:0805")
      (libsource (lib "eagle-import") (part "RESISTOR0805"))
    )
    (comp (ref "R32")
      (value "22")
      (footprint "eagle-import:0805")
      (libsource (lib "eagle-import") (part "RESISTOR0805"))
    )
    (comp (ref "R33")
      (value "10k")
      (footprint "eagle-import:0805")
      (libsource (lib "eagle-import") (part "RESISTOR0805"))
    )
    (comp (ref "R34")
      (value "10k")
      (footprint "eagle-import:0805")
      (libsource (lib "eagle-import") (part "RESISTOR0805"))
    )
    (comp (ref "R35")
      (value "10k")
      (footprint "eagle-import:0805")
      (libsource (lib "eagle-import") (part "RESISTOR0805"))
    )
    (comp (ref "R36")
      (value "10k")
      (footprint "eagle-import:0805")
      (libsource (lib "eagle-import") (part "RESISTOR0805"))
    )
    (comp (ref "R37")
      (value "2.2k")
      (footprint "eagle-import:0805")
      (libsource (lib "eagle-import") (part "RESISTOR0805"))
    )
    (comp (ref "R38")
      (value "2.2k")
      (footprint "eagle-import:0805")
      (libsource (lib "eagle-import") (part "RESISTOR0805"))
    )
    (comp (ref "R39")
      (value "10k")
      (footprint "eagle-import:0805")
      (libsource (lib "eagle-import") (part "RESISTOR0805"))
    )
    (comp (ref "R40")
      (value "10k")
      (footprint "eagle-import:0805")
      (libsource (lib "eagle-import") (part "RESISTOR0805"))
    )
    (comp (ref "R41")
      (value "1k")
      (footprint "eagle-import:0805")
      (libsource (lib "eagle-import") (part "RESISTOR0805"))
    )
    (comp (ref "R42")
      (value "10k")
      (footprint "eagle-import:0805")
      (libsource (lib "eagle-import") (part "RESISTOR0805"))
    )
    (comp (ref "R43")
      (value "10k")
      (footprint "eagle-import:0805")
      (libsource (lib "eagle-import") (part "RESISTOR0805"))
    )
    (comp (ref "R44")
      (value "10k")
      (footprint "eagle-import:0805")
      (libsource (lib "eagle-import") (part "RESISTOR0805"))
    )
    (comp (ref "RCCREF")
      (value "301k")
      (footprint "eagle-import:0805")
      (libsource (lib "eagle-import") (part "RESISTOR0805"))
    )
    (comp (ref "RF")
      (value "B4B-PH-K-S(LF)(SN)")
      (footprint "eagle-import:JST_B4B-PH-K-S(LF)(SN)")
      (fields (field (name "MF") "JST Sales") (field (name "MP") "B4B-PH-K-S_LF__SN_"))
      (libsource (lib "eagle-import") (part "B4B-PH-K-S(LF)(SN)"))
    )
    (comp (ref "RFBB")
      (value "1.07k")
      (footprint "eagle-import:0805")
      (libsource (lib "eagle-import") (part "RESISTOR0805"))
    )
    (comp (ref "RFBT")
      (value "5.62k")
      (footprint "eagle-import:0805")
      (libsource (lib "eagle-import") (part "RESISTOR0805"))
    )
    (comp (ref "RM")
      (value "B4B-PH-K-S(LF)(SN)")
      (footprint "eagle-import:JST_B4B-PH-K-S(LF)(SN)")
      (fields (field (name "MF") "JST Sales") (field (name "MP") "B4B-PH-K-S_LF__SN_"))
      (libsource (lib "eagle-import") (part "B4B-PH-K-S(LF)(SN)"))
    )
    (comp (ref "RPARALLEL")
      (value "2M")
      (footprint "eagle-import:0805")
      (libsource (lib "eagle-import") (part "RESISTOR0805"))
    )
    (comp (ref "RPI")
      (value "DF50-20DP-1V")
      (footprint "eagle-import:DF50-20DP-1V")
      (libsource (lib "eagle-import") (part "DF50-20DP-1V"))
    )
    (comp (ref "RR")
      (value "B4B-PH-K-S(LF)(SN)")
      (footprint "eagle-import:JST_B4B-PH-K-S(LF)(SN)")
      (fields (field (name "MF") "JST Sales") (field (name "MP") "B4B-PH-K-S_LF__SN_"))
      (libsource (lib "eagle-import") (part "B4B-PH-K-S(LF)(SN)"))
    )
    (comp (ref "RSERIES")
      (value "5k")
      (footprint "eagle-import:0805")
      (libsource (lib "eagle-import") (part "RESISTOR0805"))
    )
    (comp (ref "RSNS1")
      (value "5m")
      (footprint "eagle-import:2012")
      (libsource (lib "eagle-import") (part "RESISTOR2012"))
    )
    (comp (ref "RSNS2")
      (value "5m")
      (footprint "eagle-import:2012")
      (libsource (lib "eagle-import") (part "RESISTOR2012"))
    )
    (comp (ref "RSNSB")
      (value "20m")
      (footprint "eagle-import:2012")
      (libsource (lib "eagle-import") (part "RESISTOR2012"))
    )
    (comp (ref "RSNSI")
      (value "0.004")
      (footprint "eagle-import:2012")
      (libsource (lib "eagle-import") (part "RESISTOR2012"))
    )
    (comp (ref "RST")
      (value "MJTP1140ATR")
      (footprint "eagle-import:MJTP1140ATR")
      (libsource (lib "eagle-import") (part "MJTP1140ATR"))
    )
    (comp (ref "RT")
      (value "95.3k")
      (footprint "eagle-import:0805")
      (libsource (lib "eagle-import") (part "RESISTOR0805"))
    )
    (comp (ref "RX")
      (value "SJ2W")
      (footprint "eagle-import:SJ_2")
      (libsource (lib "eagle-import") (part "SJ2W"))
    )
    (comp (ref "SDO_AG")
      (value "SJ2WSJ_3")
      (footprint "eagle-import:SJ_3")
      (libsource (lib "eagle-import") (part "SJ2WSJ_3"))
    )
    (comp (ref "SDO_M")
      (value "SJ2WSJ_3")
      (footprint "eagle-import:SJ_3")
      (libsource (lib "eagle-import") (part "SJ2WSJ_3"))
    )
    (comp (ref "SERVOS")
      (value "BM12B-ZPDSS-TF")
      (footprint "eagle-import:BM12B-ZPDSS-TF")
      (libsource (lib "eagle-import") (part "BM12B-ZPDSS-TF"))
    )
    (comp (ref "SJ1")
      (value "SOLDERJUMPER")
      (footprint "eagle-import:SOLDERJUMPER_ARROW_NOPASTE")
      (libsource (lib "eagle-import") (part "SOLDERJUMPER"))
    )
    (comp (ref "SJ2")
      (value "SOLDERJUMPER")
      (footprint "eagle-import:SOLDERJUMPER_ARROW_NOPASTE")
      (libsource (lib "eagle-import") (part "SOLDERJUMPER"))
    )
    (comp (ref "SJ3")
      (value "SOLDERJUMPER")
      (footprint "eagle-import:SOLDERJUMPER_ARROW_NOPASTE")
      (libsource (lib "eagle-import") (part "SOLDERJUMPER"))
    )
    (comp (ref "SW1")
      (value "MOLEX_53398")
      (footprint "eagle-import:MOLEX_53398")
      (libsource (lib "eagle-import") (part "MOLEX_53398"))
    )
    (comp (ref "SW_PANEL")
      (value "0532610671")
      (footprint "eagle-import:MOLEX_0532610671")
      (fields (field (name "MF") "Molex, LLC"))
      (libsource (lib "eagle-import") (part "_myLib_0532610671"))
    )
    (comp (ref "T-IR")
      (value "0532610371")
      (footprint "eagle-import:MOLEX_0532610371")
      (fields (field (name "MF") "Molex, LLC"))
      (libsource (lib "eagle-import") (part "0532610371"))
    )
    (comp (ref "TX")
      (value "SJ2W")
      (footprint "eagle-import:SJ_2")
      (libsource (lib "eagle-import") (part "SJ2W"))
    )
    (comp (ref "U$5")
      (value "LM25119PSQ")
      (footprint "eagle-import:SQA32A")
      (fields (field (name "MANUFACTURER_PART_NUMBER") "LM25119PSQNOPB"))
      (libsource (lib "eagle-import") (part "LM25119PSQ/NOPB"))
    )
    (comp (ref "U$11")
      (value "NTF5P03T3")
      (footprint "eagle-import:SOT223")
      (libsource (lib "eagle-import") (part "NTF5P03T3"))
    )
    (comp (ref "U$12")
      (value "NTF5P03T3")
      (footprint "eagle-import:SOT223")
      (libsource (lib "eagle-import") (part "NTF5P03T3"))
    )
    (comp (ref "U1")
      (value "LSM9DS1TR")
      (footprint "eagle-import:PQFN43P300X350X102-24N")
      (fields (field (name "DIGI-KEY_PART_NUMBER") "497-14946-1-ND") (field (name "MF") "STMicroelectronics"))
      (libsource (lib "eagle-import") (part "LSM9DS1TR"))
    )
    (comp (ref "U2")
      (value "STM32F415VGT6")
      (footprint "eagle-import:QFP50P1600X1600X160-100N")
      (fields (field (name "MF") "STMicroelectronics"))
      (libsource (lib "eagle-import") (part "STM32F415VGT6"))
    )
    (comp (ref "U3")
      (value "CSD87330Q3D")
      (footprint "eagle-import:DQZ8_1P8X2P7")
      (libsource (lib "eagle-import") (part "CSD87330Q3DCSD87335Q3D"))
    )
    (comp (ref "U4")
      (value "CSD87350Q5D")
      (footprint "eagle-import:DQY8_3P2X4P3")
      (libsource (lib "eagle-import") (part "CSD87350Q5D"))
    )
    (comp (ref "U5")
      (value "TEXAS_INSTRUMENTS_ADC101C021CIMK-NOPBTEXAS_INSTRUMENTS_ADC101C021CIMK-NOPB_0_0")
      (footprint "eagle-import:TEXAS_INSTRUMENTS_ADC101C021CIMK-NOPB_0")
      (fields
        (field (name "DIGIKEY_PART_NUMBER") "ADC101C021CIMK/NOPBCT-ND")
        (field (name "MF") "Texas Instruments")
        (field (name "MOUSER_PART_NUMBER") "926-AD101C021CIMKNPB")
      )
      (libsource (lib "eagle-import") (part "TEXAS_INSTRUMENTS_ADC101C021CIMK-NOPBTEXAS_INSTRUMENTS_ADC101C021CIMK-NOPB_0_0"))
    )
    (comp (ref "U6")
      (value "CSD87350Q5D")
      (footprint "eagle-import:DQY8_3P2X4P3")
      (libsource (lib "eagle-import") (part "CSD87350Q5D"))
    )
    (comp (ref "U7")
      (value "CRE1S0505MC")
      (footprint "eagle-import:SOIC254P1110X700-5N")
      (fields (field (name "MF") "Recom Power") (field (name "MP") "R1SE-0505"))
      (libsource (lib "eagle-import") (part "R1SE-0505"))
    )
    (comp (ref "USER")
      (value "MJTP1140ATR")
      (footprint "eagle-import:MJTP1140ATR")
      (libsource (lib "eagle-import") (part "MJTP1140ATR"))
    )
  )
  (nets
    (net (code "1") (name "+3V3") (class "Default")
      (node (ref "3V3") (pin "VOUT") (pinfunction "VOUT_VOUT") (pintype "bidirectional"))
      (node (ref "BT") (pin "5") (pinfunction "+3V3_5") (pintype "power_in"))
      (node (ref "C69") (pin "1") (pinfunction "P$1_1") (pintype "passive"))
      (node (ref "C75") (pin "1") (pinfunction "P$1_1") (pintype "passive"))
      (node (ref "C76") (pin "1") (pinfunction "P$1_1") (pintype "passive"))
      (node (ref "DOCK") (pin "P$2") (pinfunction "P$2_P$2") (pintype "bidirectional"))
      (node (ref "EYES/GEST") (pin "4") (pinfunction "4_4") (pintype "passive"))
      (node (ref "FB1") (pin "2") (pinfunction "P$2_2") (pintype "passive"))
      (node (ref "HOOD") (pin "2") (pinfunction "2_2") (pintype "passive"))
      (node (ref "JPF") (pin "P$3") (pinfunction "3_P$3") (pintype "passive"))
      (node (ref "JPF1") (pin "P$1") (pinfunction "1_P$1") (pintype "passive"))
      (node (ref "JTAG") (pin "1") (pinfunction "1_1") (pintype "passive"))
      (node (ref "LTC4015") (pin "3") (pinfunction "DVCC_3") (pintype "power_in"))
      (node (ref "Q14") (pin "E") (pinfunction "E_E") (pintype "passive"))
      (node (ref "Q7") (pin "E") (pinfunction "E_E") (pintype "passive"))
      (node (ref "R14") (pin "2") (pinfunction "2_2") (pintype "passive"))
      (node (ref "R26") (pin "1") (pinfunction "1_1") (pintype "passive"))
      (node (ref "R27") (pin "2") (pinfunction "2_2") (pintype "passive"))
      (node (ref "R37") (pin "1") (pinfunction "1_1") (pintype "passive"))
      (node (ref "R38") (pin "1") (pinfunction "1_1") (pintype "passive"))
      (node (ref "R7") (pin "1") (pinfunction "1_1") (pintype "passive"))
      (node (ref "SDO_AG") (pin "P$1") (pinfunction "1_P$1") (pintype "passive"))
      (node (ref "SDO_M") (pin "P$1") (pinfunction "1_P$1") (pintype "passive"))
      (node (ref "SJ1") (pin "1") (pinfunction "1_1") (pintype "passive"))
      (node (ref "SJ2") (pin "1") (pinfunction "1_1") (pintype "passive"))
      (node (ref "SJ3") (pin "1") (pinfunction "1_1") (pintype "passive"))
      (node (ref "SW_PANEL") (pin "2") (pinfunction "2_2") (pintype "passive"))
      (node (ref "SW_PANEL") (pin "4") (pinfunction "4_4") (pintype "passive"))
      (node (ref "U1") (pin "7") (pinfunction "CS_A/G_7") (pintype "input"))
      (node (ref "U1") (pin "8") (pinfunction "CS_M_8") (pintype "input"))
      (node (ref "USER") (pin "P$2") (pinfunction "P$2_P$2") (pintype "bidirectional"))
    )
    (net (code "2") (name "2P5VCC") (class "Default")
      (node (ref "C8") (pin "1") (pinfunction "P$1_1") (pintype "passive"))
      (node (ref "LTC4015") (pin "22") (pinfunction "2P5VCC_22") (pintype "power_in"))
      (node (ref "R13") (pin "2") (pinfunction "2_2") (pintype "passive"))
    )
    (net (code "3") (name "5.0V") (class "Default")
      (node (ref "5V") (pin "7") (pinfunction "VOUT_7") (pintype "output"))
      (node (ref "C100") (pin "1") (pinfunction "P$1_1") (pintype "passive"))
      (node (ref "C70") (pin "1") (pinfunction "P$1_1") (pintype "passive"))
      (node (ref "C77") (pin "1") (pinfunction "P$1_1") (pintype "passive"))
      (node (ref "C81") (pin "1") (pinfunction "P$1_1") (pintype "passive"))
      (node (ref "C83") (pin "1") (pinfunction "P$1_1") (pintype "passive"))
      (node (ref "C84") (pin "1") (pinfunction "P$1_1") (pintype "passive"))
      (node (ref "C87") (pin "1") (pinfunction "P$1_1") (pintype "passive"))
      (node (ref "JPF") (pin "P$1") (pinfunction "1_P$1") (pintype "passive"))
      (node (ref "JPF1") (pin "P$3") (pinfunction "3_P$3") (pintype "passive"))
      (node (ref "Q1") (pin "2") (pinfunction "S_2") (pintype "passive"))
      (node (ref "Q10") (pin "2") (pinfunction "S_2") (pintype "passive"))
      (node (ref "Q12") (pin "2") (pinfunction "S_2") (pintype "passive"))
      (node (ref "Q4") (pin "2") (pinfunction "S_2") (pintype "passive"))
      (node (ref "Q8") (pin "2") (pinfunction "S_2") (pintype "passive"))
      (node (ref "R34") (pin "1") (pinfunction "1_1") (pintype "passive"))
      (node (ref "R35") (pin "1") (pinfunction "1_1") (pintype "passive"))
      (node (ref "R36") (pin "1") (pinfunction "1_1") (pintype "passive"))
      (node (ref "R39") (pin "1") (pinfunction "1_1") (pintype "passive"))
      (node (ref "R40") (pin "1") (pinfunction "1_1") (pintype "passive"))
      (node (ref "RFBT") (pin "2") (pinfunction "2_2") (pintype "passive"))
      (node (ref "T-IR") (pin "1") (pinfunction "1_1") (pintype "passive"))
      (node (ref "U7") (pin "3") (pinfunction "+VIN_3") (pintype "input"))
    )
    (net (code "4") (name "AMP_PWR") (class "Default")
      (node (ref "C93") (pin "1") (pinfunction "P$1_1") (pintype "passive"))
      (node (ref "L5") (pin "2") (pinfunction "2_2") (pintype "passive"))
      (node (ref "RPI") (pin "P$20") (pinfunction "P$20_P$20") (pintype "bidirectional"))
    )
    (net (code "5") (name "BT_CLK") (class "Default")
      (node (ref "BT") (pin "7") (pinfunction "SPI_CLK_7") (pintype "input"))
      (node (ref "U2") (pin "78") (pinfunction "PC10_78") (pintype "bidirectional"))
    )
    (net (code "6") (name "BT_CS") (class "Default")
      (node (ref "BT") (pin "10") (pinfunction "SPI_CS_10") (pintype "input"))
      (node (ref "U2") (pin "81") (pinfunction "PD0_81") (pintype "bidirectional"))
    )
    (net (code "7") (name "BT_MISO") (class "Default")
      (node (ref "BT") (pin "8") (pinfunction "SPI_MISO_8") (pintype "output"))
      (node (ref "U2") (pin "79") (pinfunction "PC11_79") (pintype "bidirectional"))
    )
    (net (code "8") (name "BT_MOSI") (class "Default")
      (node (ref "BT") (pin "9") (pinfunction "SPI_MOSI_9") (pintype "input"))
      (node (ref "U2") (pin "80") (pinfunction "PC12_80") (pintype "bidirectional"))
    )
    (net (code "9") (name "BT_RESET") (class "Default")
      (node (ref "BT") (pin "11") (pinfunction "BT_RESET_11") (pintype "input"))
      (node (ref "R26") (pin "2") (pinfunction "2_2") (pintype "passive"))
      (node (ref "U2") (pin "83") (pinfunction "PD2_83") (pintype "bidirectional"))
    )
    (net (code "10") (name "DC_IN") (class "Default")
      (node (ref "C15") (pin "1") (pinfunction "P$1_1") (pintype "passive"))
      (node (ref "C16") (pin "1") (pinfunction "P$1_1") (pintype "passive"))
      (node (ref "C17") (pin "1") (pinfunction "P$1_1") (pintype "passive"))
      (node (ref "C18") (pin "1") (pinfunction "P$1_1") (pintype "passive"))
      (node (ref "C28") (pin "+") (pinfunction "+_+") (pintype "passive"))
      (node (ref "D1") (pin "3") (pinfunction "A2_3") (pintype "passive"))
      (node (ref "DC-IN") (pin "1") (pinfunction "1_1") (pintype "passive"))
      (node (ref "LTC4015") (pin "35") (pinfunction "VIN_35") (pintype "power_in"))
      (node (ref "M5") (pin "1") (pinfunction "S_1") (pintype "passive"))
      (node (ref "M5") (pin "2") (pinfunction "S_2") (pintype "passive"))
      (node (ref "M5") (pin "3") (pinfunction "S_3") (pintype "passive"))
    )
    (net (code "11") (name "DISCHARGE") (class "Default")
      (node (ref "C4") (pin "1") (pinfunction "P$1_1") (pintype "passive"))
      (node (ref "C5") (pin "2") (pinfunction "P$2_2") (pintype "passive"))
      (node (ref "L1") (pin "P$2") (pinfunction "P$2_P$2") (pintype "bidirectional"))
      (node (ref "LTC4015") (pin "20") (pinfunction "CSP_20") (pintype "bidirectional"))
      (node (ref "M4") (pin "5") (pinfunction "2_DRAIN_5") (pintype "passive"))
      (node (ref "M4") (pin "6") (pinfunction "2_DRAIN_6") (pintype "passive"))
      (node (ref "M4") (pin "7") (pinfunction "2_DRAIN_7") (pintype "passive"))
      (node (ref "M4") (pin "8") (pinfunction "2_DRAIN_8") (pintype "passive"))
      (node (ref "RSNSB") (pin "2") (pinfunction "2_2") (pintype "passive"))
    )
    (net (code "12") (name "DOCK_SENS") (class "Default")
      (node (ref "C71") (pin "1") (pinfunction "P$1_1") (pintype "passive"))
      (node (ref "DOCK") (pin "P$1") (pinfunction "P$1_P$1") (pintype "bidirectional"))
      (node (ref "R33") (pin "2") (pinfunction "2_2") (pintype "passive"))
      (node (ref "U2") (pin "82") (pinfunction "PD1_82") (pintype "bidirectional"))
    )
    (net (code "13") (name "EYES_RST") (class "Default")
      (node (ref "EYES/GEST") (pin "3") (pinfunction "3_3") (pintype "passive"))
      (node (ref "U2") (pin "58") (pinfunction "PD11_58") (pintype "bidirectional"))
    )
    (net (code "14") (name "FLEX_OLED_CLK") (class "Default")
      (node (ref "FLEX_OLED") (pin "4") (pinfunction "4_4") (pintype "passive"))
      (node (ref "U2") (pin "52") (pinfunction "PB13_52") (pintype "bidirectional"))
    )
    (net (code "15") (name "FLEX_OLED_CS") (class "Default")
      (node (ref "FLEX_OLED") (pin "5") (pinfunction "5_5") (pintype "passive"))
      (node (ref "U2") (pin "51") (pinfunction "PB12_51") (pintype "bidirectional"))
    )
    (net (code "16") (name "FLEX_OLED_MOSI") (class "Default")
      (node (ref "FLEX_OLED") (pin "2") (pinfunction "2_2") (pintype "passive"))
      (node (ref "U2") (pin "54") (pinfunction "PB15_54") (pintype "bidirectional"))
    )
    (net (code "17") (name "FLEX_OLED_RST") (class "Default")
      (node (ref "FLEX_OLED") (pin "3") (pinfunction "3_3") (pintype "passive"))
      (node (ref "U2") (pin "53") (pinfunction "PB14_53") (pintype "bidirectional"))
    )
    (net (code "18") (name "GND") (class "Default")
      (node (ref "3V3") (pin "GND") (pinfunction "GND_GND") (pintype "bidirectional"))
      (node (ref "5V") (pin "2") (pinfunction "SYNC_2") (pintype "input"))
      (node (ref "5V") (pin "4") (pinfunction "AGND_4") (pintype "power_in"))
      (node (ref "5V") (pin "8") (pinfunction "8_8") (pintype "passive"))
      (node (ref "BATTERY") (pin "1") (pinfunction "1_1") (pintype "passive"))
      (node (ref "BT") (pin "6") (pinfunction "GND_6") (pintype "power_in"))
      (node (ref "BUZZ") (pin "N") (pinfunction "N_N") (pintype "passive"))
      (node (ref "C100") (pin "2") (pinfunction "P$2_2") (pintype "passive"))
      (node (ref "C101") (pin "2") (pinfunction "P$2_2") (pintype "passive"))
      (node (ref "C13") (pin "2") (pinfunction "P$2_2") (pintype "passive"))
      (node (ref "C14") (pin "2") (pinfunction "P$2_2") (pintype "passive"))
      (node (ref "C15") (pin "2") (pinfunction "P$2_2") (pintype "passive"))
      (node (ref "C16") (pin "2") (pinfunction "P$2_2") (pintype "passive"))
      (node (ref "C17") (pin "2") (pinfunction "P$2_2") (pintype "passive"))
      (node (ref "C18") (pin "2") (pinfunction "P$2_2") (pintype "passive"))
      (node (ref "C19") (pin "2") (pinfunction "P$2_2") (pintype "passive"))
      (node (ref "C2") (pin "2") (pinfunction "P$2_2") (pintype "passive"))
      (node (ref "C20") (pin "2") (pinfunction "P$2_2") (pintype "passive"))
      (node (ref "C21") (pin "2") (pinfunction "P$2_2") (pintype "passive"))
      (node (ref "C22") (pin "2") (pinfunction "P$2_2") (pintype "passive"))
      (node (ref "C23") (pin "2") (pinfunction "P$2_2") (pintype "passive"))
      (node (ref "C24") (pin "2") (pinfunction "P$2_2") (pintype "passive"))
      (node (ref "C25") (pin "2") (pinfunction "P$2_2") (pintype "passive"))
      (node (ref "C26") (pin "2") (pinfunction "P$2_2") (pintype "passive"))
      (node (ref "C27") (pin "2") (pinfunction "P$2_2") (pintype "passive"))
      (node (ref "C28") (pin "-") (pinfunction "-_-") (pintype "passive"))
      (node (ref "C29") (pin "2") (pinfunction "P$2_2") (pintype "passive"))
      (node (ref "C30") (pin "2") (pinfunction "P$2_2") (pintype "passive"))
      (node (ref "C31") (pin "2") (pinfunction "P$2_2") (pintype "passive"))
      (node (ref "C32") (pin "-") (pinfunction "-_-") (pintype "passive"))
      (node (ref "C33") (pin "1") (pinfunction "P$1_1") (pintype "passive"))
      (node (ref "C34") (pin "1") (pinfunction "P$1_1") (pintype "passive"))
      (node (ref "C35") (pin "1") (pinfunction "P$1_1") (pintype "passive"))
      (node (ref "C38") (pin "-") (pinfunction "-_-") (pintype "passive"))
      (node (ref "C43") (pin "-") (pinfunction "-_-") (pintype "passive"))
      (node (ref "C44") (pin "-") (pinfunction "-_-") (pintype "passive"))
      (node (ref "C45") (pin "-") (pinfunction "-_-") (pintype "passive"))
      (node (ref "C46") (pin "-") (pinfunction "-_-") (pintype "passive"))
      (node (ref "C47") (pin "2") (pinfunction "P$2_2") (pintype "passive"))
      (node (ref "C48") (pin "2") (pinfunction "P$2_2") (pintype "passive"))
      (node (ref "C49") (pin "2") (pinfunction "P$2_2") (pintype "passive"))
      (node (ref "C50") (pin "2") (pinfunction "P$2_2") (pintype "passive"))
      (node (ref "C51") (pin "1") (pinfunction "P$1_1") (pintype "passive"))
      (node (ref "C52") (pin "2") (pinfunction "P$2_2") (pintype "passive"))
      (node (ref "C53") (pin "2") (pinfunction "P$2_2") (pintype "passive"))
      (node (ref "C54") (pin "2") (pinfunction "P$2_2") (pintype "passive"))
      (node (ref "C55") (pin "2") (pinfunction "P$2_2") (pintype "passive"))
      (node (ref "C56") (pin "2") (pinfunction "P$2_2") (pintype "passive"))
      (node (ref "C57") (pin "1") (pinfunction "P$1_1") (pintype "passive"))
      (node (ref "C58") (pin "1") (pinfunction "P$1_1") (pintype "passive"))
      (node (ref "C59") (pin "1") (pinfunction "P$1_1") (pintype "passive"))
      (node (ref "C6") (pin "2") (pinfunction "P$2_2") (pintype "passive"))
      (node (ref "C60") (pin "1") (pinfunction "P$1_1") (pintype "passive"))
      (node (ref "C61") (pin "1") (pinfunction "P$1_1") (pintype "passive"))
      (node (ref "C62") (pin "1") (pinfunction "P$1_1") (pintype "passive"))
      (node (ref "C63") (pin "2") (pinfunction "P$2_2") (pintype "passive"))
      (node (ref "C64") (pin "2") (pinfunction "P$2_2") (pintype "passive"))
      (node (ref "C65") (pin "1") (pinfunction "P$1_1") (pintype "passive"))
      (node (ref "C66") (pin "1") (pinfunction "P$1_1") (pintype "passive"))
      (node (ref "C67") (pin "2") (pinfunction "P$2_2") (pintype "passive"))
      (node (ref "C68") (pin "2") (pinfunction "P$2_2") (pintype "passive"))
      (node (ref "C69") (pin "2") (pinfunction "P$2_2") (pintype "passive"))
      (node (ref "C7") (pin "2") (pinfunction "P$2_2") (pintype "passive"))
      (node (ref "C70") (pin "2") (pinfunction "P$2_2") (pintype "passive"))
      (node (ref "C71") (pin "2") (pinfunction "P$2_2") (pintype "passive"))
      (node (ref "C72") (pin "2") (pinfunction "P$2_2") (pintype "passive"))
      (node (ref "C73") (pin "2") (pinfunction "P$2_2") (pintype "passive"))
      (node (ref "C74") (pin "2") (pinfunction "P$2_2") (pintype "passive"))
      (node (ref "C75") (pin "2") (pinfunction "P$2_2") (pintype "passive"))
      (node (ref "C76") (pin "2") (pinfunction "P$2_2") (pintype "passive"))
      (node (ref "C77") (pin "2") (pinfunction "P$2_2") (pintype "passive"))
      (node (ref "C78") (pin "2") (pinfunction "P$2_2") (pintype "passive"))
      (node (ref "C79") (pin "2") (pinfunction "P$2_2") (pintype "passive"))
      (node (ref "C8") (pin "2") (pinfunction "P$2_2") (pintype "passive"))
      (node (ref "C80") (pin "2") (pinfunction "P$2_2") (pintype "passive"))
      (node (ref "C81") (pin "2") (pinfunction "P$2_2") (pintype "passive"))
      (node (ref "C82") (pin "2") (pinfunction "P$2_2") (pintype "passive"))
      (node (ref "C83") (pin "2") (pinfunction "P$2_2") (pintype "passive"))
      (node (ref "C84") (pin "2") (pinfunction "P$2_2") (pintype "passive"))
      (node (ref "C85") (pin "2") (pinfunction "P$2_2") (pintype "passive"))
      (node (ref "C86") (pin "2") (pinfunction "P$2_2") (pintype "passive"))
      (node (ref "C87") (pin "2") (pinfunction "P$2_2") (pintype "passive"))
      (node (ref "C88") (pin "1") (pinfunction "P$1_1") (pintype "passive"))
      (node (ref "C89") (pin "1") (pinfunction "P$1_1") (pintype "passive"))
      (node (ref "C90") (pin "2") (pinfunction "P$2_2") (pintype "passive"))
      (node (ref "C91") (pin "-") (pinfunction "-_-") (pintype "passive"))
      (node (ref "C92") (pin "-") (pinfunction "-_-") (pintype "passive"))
      (node (ref "C93") (pin "2") (pinfunction "P$2_2") (pintype "passive"))
      (node (ref "C94") (pin "2") (pinfunction "P$2_2") (pintype "passive"))
      (node (ref "C95") (pin "2") (pinfunction "P$2_2") (pintype "passive"))
      (node (ref "C96") (pin "2") (pinfunction "P$2_2") (pintype "passive"))
      (node (ref "C97") (pin "2") (pinfunction "P$2_2") (pintype "passive"))
      (node (ref "C98") (pin "2") (pinfunction "P$2_2") (pintype "passive"))
      (node (ref "C99") (pin "2") (pinfunction "P$2_2") (pintype "passive"))
      (node (ref "CHEM0") (pin "3") (pinfunction "3_3") (pintype "passive"))
      (node (ref "CHEM1") (pin "3") (pinfunction "3_3") (pintype "passive"))
      (node (ref "DC-IN") (pin "2") (pinfunction "2_2") (pintype "passive"))
      (node (ref "EYES/GEST") (pin "5") (pinfunction "5_5") (pintype "passive"))
      (node (ref "EYES/GEST") (pin "S1") (pinfunction "SHIELD_S1") (pintype "passive"))
      (node (ref "EYES/GEST") (pin "S2") (pinfunction "SHIELD_S2") (pintype "passive"))
      (node (ref "FAN") (pin "2") (pinfunction "2_2") (pintype "passive"))
      (node (ref "FLEX_OLED") (pin "6") (pinfunction "6_6") (pintype "passive"))
      (node (ref "FLEX_OLED") (pin "S1") (pinfunction "SHIELD_S1") (pintype "passive"))
      (node (ref "FLEX_OLED") (pin "S2") (pinfunction "SHIELD_S2") (pintype "passive"))
      (node (ref "HOOD") (pin "6") (pinfunction "6_6") (pintype "passive"))
      (node (ref "HOOD") (pin "S1") (pinfunction "SHIELD_S1") (pintype "passive"))
      (node (ref "HOOD") (pin "S2") (pinfunction "SHIELD_S2") (pintype "passive"))
      (node (ref "IC1") (pin "1") (pinfunction "GND_1") (pintype "power_in"))
      (node (ref "JTAG") (pin "3") (pinfunction "3_3") (pintype "passive"))
      (node (ref "JTAG") (pin "5") (pinfunction "5_5") (pintype "passive"))
      (node (ref "LF") (pin "4") (pinfunction "4_4") (pintype "passive"))
      (node (ref "LM") (pin "4") (pinfunction "4_4") (pintype "passive"))
      (node (ref "LR") (pin "4") (pinfunction "4_4") (pintype "passive"))
      (node (ref "LTC4015") (pin "13") (pinfunction "EQ_13") (pintype "input"))
      (node (ref "LTC4015") (pin "14") (pinfunction "GND_14") (pintype "power_in"))
      (node (ref "LTC4015") (pin "2") (pinfunction "CELLS2_2") (pintype "bidirectional"))
      (node (ref "LTC4015") (pin "21") (pinfunction "MPPT_21") (pintype "input"))
      (node (ref "LTC4015") (pin "39") (pinfunction "EXP_39") (pintype "passive"))
      (node (ref "LTC4015") (pin "7") (pinfunction "SGND_7") (pintype "power_in"))
      (node (ref "NTC") (pin "1") (pinfunction "1_1") (pintype "passive"))
      (node (ref "NTC1") (pin "4") (pinfunction "GND_4") (pintype "power_in"))
      (node (ref "NTC1") (pin "5") (pinfunction "A2_5") (pintype "bidirectional"))
      (node (ref "NTC1") (pin "6") (pinfunction "A1_6") (pintype "bidirectional"))
      (node (ref "NTC1") (pin "7") (pinfunction "A0_7") (pintype "bidirectional"))
      (node (ref "NTC2") (pin "4") (pinfunction "GND_4") (pintype "power_in"))
      (node (ref "NTC2") (pin "5") (pinfunction "A2_5") (pintype "bidirectional"))
      (node (ref "NTC2") (pin "6") (pinfunction "A1_6") (pintype "bidirectional"))
      (node (ref "Q11") (pin "E") (pinfunction "E_E") (pintype "passive"))
      (node (ref "Q13") (pin "E") (pinfunction "E_E") (pintype "passive"))
      (node (ref "Q2") (pin "E") (pinfunction "E_E") (pintype "passive"))
      (node (ref "Q3") (pin "E") (pinfunction "E_E") (pintype "passive"))
      (node (ref "Q5") (pin "E") (pinfunction "E_E") (pintype "passive"))
      (node (ref "Q6") (pin "E") (pinfunction "E_E") (pintype "passive"))
      (node (ref "Q9") (pin "E") (pinfunction "E_E") (pintype "passive"))
      (node (ref "R10") (pin "2") (pinfunction "2_2") (pintype "passive"))
      (node (ref "R11") (pin "1") (pinfunction "1_1") (pintype "passive"))
      (node (ref "R15") (pin "1") (pinfunction "1_1") (pintype "passive"))
      (node (ref "R18") (pin "1") (pinfunction "1_1") (pintype "passive"))
      (node (ref "R22") (pin "1") (pinfunction "1_1") (pintype "passive"))
      (node (ref "R24") (pin "1") (pinfunction "1_1") (pintype "passive"))
      (node (ref "R28") (pin "1") (pinfunction "1_1") (pintype "passive"))
      (node (ref "R3") (pin "1") (pinfunction "1_1") (pintype "passive"))
      (node (ref "R31") (pin "1") (pinfunction "1_1") (pintype "passive"))
      (node (ref "R33") (pin "1") (pinfunction "1_1") (pintype "passive"))
      (node (ref "R4") (pin "2") (pinfunction "2_2") (pintype "passive"))
      (node (ref "R43") (pin "2") (pinfunction "2_2") (pintype "passive"))
      (node (ref "R44") (pin "2") (pinfunction "2_2") (pintype "passive"))
      (node (ref "R5") (pin "2") (pinfunction "2_2") (pintype "passive"))
      (node (ref "R6") (pin "2") (pinfunction "2_2") (pintype "passive"))
      (node (ref "R8") (pin "1") (pinfunction "1_1") (pintype "passive"))
      (node (ref "R9") (pin "1") (pinfunction "1_1") (pintype "passive"))
      (node (ref "RF") (pin "4") (pinfunction "4_4") (pintype "passive"))
      (node (ref "RFBB") (pin "2") (pinfunction "2_2") (pintype "passive"))
      (node (ref "RM") (pin "4") (pinfunction "4_4") (pintype "passive"))
      (node (ref "RPARALLEL") (pin "2") (pinfunction "2_2") (pintype "passive"))
      (node (ref "RPI") (pin "P$10") (pinfunction "P$10_P$10") (pintype "bidirectional"))
      (node (ref "RPI") (pin "P$12") (pinfunction "P$12_P$12") (pintype "bidirectional"))
      (node (ref "RPI") (pin "P$18") (pinfunction "P$18_P$18") (pintype "bidirectional"))
      (node (ref "RR") (pin "4") (pinfunction "4_4") (pintype "passive"))
      (node (ref "RSNS1") (pin "1") (pinfunction "1_1") (pintype "passive"))
      (node (ref "RSNS2") (pin "1") (pinfunction "1_1") (pintype "passive"))
      (node (ref "RT") (pin "2") (pinfunction "2_2") (pintype "passive"))
      (node (ref "SDO_AG") (pin "P$3") (pinfunction "3_P$3") (pintype "passive"))
      (node (ref "SDO_M") (pin "P$3") (pinfunction "3_P$3") (pintype "passive"))
      (node (ref "SERVOS") (pin "P$10") (pinfunction "P$10_P$10") (pintype "bidirectional"))
      (node (ref "SERVOS") (pin "P$3") (pinfunction "P$3_P$3") (pintype "bidirectional"))
      (node (ref "SERVOS") (pin "P$6") (pinfunction "P$6_P$6") (pintype "bidirectional"))
      (node (ref "SERVOS") (pin "P$7") (pinfunction "P$7_P$7") (pintype "bidirectional"))
      (node (ref "SW_PANEL") (pin "S1") (pinfunction "SHIELD_S1") (pintype "passive"))
      (node (ref "SW_PANEL") (pin "S2") (pinfunction "SHIELD_S2") (pintype "passive"))
      (node (ref "T-IR") (pin "2") (pinfunction "2_2") (pintype "passive"))
      (node (ref "U$5") (pin "21") (pinfunction "CSG2_21") (pintype "passive"))
      (node (ref "U$5") (pin "22") (pinfunction "PGND2_22") (pintype "passive"))
      (node (ref "U$5") (pin "3") (pinfunction "PGND1_3") (pintype "passive"))
      (node (ref "U$5") (pin "33") (pinfunction "PAD_33") (pintype "bidirectional"))
      (node (ref "U$5") (pin "4") (pinfunction "CSG1_4") (pintype "passive"))
      (node (ref "U1") (pin "14") (pinfunction "RES_14") (pintype "bidirectional"))
      (node (ref "U1") (pin "15") (pinfunction "RES_15") (pintype "bidirectional"))
      (node (ref "U1") (pin "16") (pinfunction "RES_16") (pintype "bidirectional"))
      (node (ref "U1") (pin "17") (pinfunction "RES_17") (pintype "bidirectional"))
      (node (ref "U1") (pin "18") (pinfunction "RES_18") (pintype "bidirectional"))
      (node (ref "U1") (pin "19") (pinfunction "GND_19") (pintype "power_in"))
      (node (ref "U1") (pin "20") (pinfunction "GND_20") (pintype "power_in"))
      (node (ref "U2") (pin "10") (pinfunction "VSS-3_10") (pintype "power_in"))
      (node (ref "U2") (pin "20") (pinfunction "VSSA_20") (pintype "power_in"))
      (node (ref "U2") (pin "27") (pinfunction "VSS-2_27") (pintype "power_in"))
      (node (ref "U2") (pin "74") (pinfunction "VSS_74") (pintype "power_in"))
      (node (ref "U2") (pin "99") (pinfunction "VSS-1_99") (pintype "power_in"))
      (node (ref "U3") (pin "9") (pinfunction "PGND_9") (pintype "power_in"))
      (node (ref "U5") (pin "2") (pinfunction "GND_2") (pintype "bidirectional"))
      (node (ref "U7") (pin "1") (pinfunction "-VIN_1") (pintype "input"))
      (node (ref "U7") (pin "7") (pinfunction "-VOUT_7") (pintype "output"))
    )
    (net (code "19") (name "HEAD_PITCH") (class "Default")
      (node (ref "SERVOS") (pin "P$1") (pinfunction "P$1_P$1") (pintype "bidirectional"))
      (node (ref "U2") (pin "61") (pinfunction "PD14_61") (pintype "bidirectional"))
    )
    (net (code "20") (name "HEAD_YAW") (class "Default")
      (node (ref "SERVOS") (pin "P$12") (pinfunction "P$12_P$12") (pintype "bidirectional"))
      (node (ref "U2") (pin "60") (pinfunction "PD13_60") (pintype "bidirectional"))
    )
    (net (code "21") (name "HOOD_SW1") (class "Default")
      (node (ref "HOOD") (pin "3") (pinfunction "3_3") (pintype "passive"))
      (node (ref "U2") (pin "65") (pinfunction "PC8_65") (pintype "bidirectional"))
    )
    (net (code "22") (name "HOOD_SW2") (class "Default")
      (node (ref "HOOD") (pin "1") (pinfunction "1_1") (pintype "passive"))
      (node (ref "U2") (pin "66") (pinfunction "PC9_66") (pintype "bidirectional"))
    )
    (net (code "23") (name "I2C1_SCL_HEAD") (class "Default")
      (node (ref "EYES/GEST") (pin "2") (pinfunction "2_2") (pintype "passive"))
      (node (ref "R37") (pin "2") (pinfunction "2_2") (pintype "passive"))
      (node (ref "U2") (pin "92") (pinfunction "PB6_92") (pintype "bidirectional"))
    )
    (net (code "24") (name "I2C1_SDA_HEAD") (class "Default")
      (node (ref "EYES/GEST") (pin "1") (pinfunction "1_1") (pintype "passive"))
      (node (ref "R38") (pin "2") (pinfunction "2_2") (pintype "passive"))
      (node (ref "U2") (pin "93") (pinfunction "PB7_93") (pintype "bidirectional"))
    )
    (net (code "25") (name "INTVCC") (class "Default")
      (node (ref "C2") (pin "1") (pinfunction "P$1_1") (pintype "passive"))
      (node (ref "C27") (pin "1") (pinfunction "P$1_1") (pintype "passive"))
      (node (ref "CHEM0") (pin "1") (pinfunction "1_1") (pintype "passive"))
      (node (ref "CHEM1") (pin "1") (pinfunction "1_1") (pintype "passive"))
      (node (ref "D2") (pin "A") (pinfunction "A_A") (pintype "passive"))
      (node (ref "LTC4015") (pin "1") (pinfunction "CELLS1_1") (pintype "bidirectional"))
      (node (ref "LTC4015") (pin "27") (pinfunction "DRVCC_27") (pintype "power_in"))
      (node (ref "LTC4015") (pin "28") (pinfunction "INTVCC_28") (pintype "power_in"))
      (node (ref "LTC4015") (pin "38") (pinfunction "CELLS0_38") (pintype "bidirectional"))
    )
    (net (code "26") (name "JTAG_NRST") (class "Default")
      (node (ref "C1") (pin "1") (pinfunction "P$1_1") (pintype "passive"))
      (node (ref "R14") (pin "1") (pinfunction "1_1") (pintype "passive"))
      (node (ref "R2") (pin "2") (pinfunction "2_2") (pintype "passive"))
      (node (ref "R29") (pin "1") (pinfunction "1_1") (pintype "passive"))
      (node (ref "R30") (pin "1") (pinfunction "1_1") (pintype "passive"))
      (node (ref "RST") (pin "P$2") (pinfunction "P$2_P$2") (pintype "bidirectional"))
    )
    (net (code "27") (name "JTAG_TCK") (class "Default")
      (node (ref "JTAG") (pin "4") (pinfunction "4_4") (pintype "passive"))
      (node (ref "U2") (pin "76") (pinfunction "PA14/JTCLK_76") (pintype "bidirectional"))
    )
    (net (code "28") (name "JTAG_TDI") (class "Default")
      (node (ref "JTAG") (pin "8") (pinfunction "8_8") (pintype "passive"))
      (node (ref "U2") (pin "77") (pinfunction "PA15/JTDI_77") (pintype "bidirectional"))
    )
    (net (code "29") (name "JTAG_TDO") (class "Default")
      (node (ref "R1") (pin "2") (pinfunction "2_2") (pintype "passive"))
      (node (ref "U2") (pin "89") (pinfunction "PB3/JTDO_89") (pintype "bidirectional"))
    )
    (net (code "30") (name "JTAG_TMS") (class "Default")
      (node (ref "JTAG") (pin "2") (pinfunction "2_2") (pintype "passive"))
      (node (ref "U2") (pin "72") (pinfunction "PA13/JTMS_72") (pintype "bidirectional"))
    )
    (net (code "31") (name "KL15") (class "Default")
      (node (ref "D4") (pin "1") (pinfunction "A1_1") (pintype "passive"))
      (node (ref "ON_OFF") (pin "P$1") (pinfunction "P$1_P$1") (pintype "bidirectional"))
      (node (ref "Q6") (pin "B") (pinfunction "B_B") (pintype "passive"))
    )
    (net (code "32") (name "LED_ACT") (class "Default")
      (node (ref "ACT") (pin "A") (pinfunction "A_A") (pintype "passive"))
      (node (ref "U2") (pin "68") (pinfunction "PA9_68") (pintype "bidirectional"))
    )
    (net (code "33") (name "LED_A_PI_BUTT") (class "Default")
      (node (ref "SW_PANEL") (pin "6") (pinfunction "6_6") (pintype "passive"))
      (node (ref "U2") (pin "44") (pinfunction "PE13_44") (pintype "bidirectional"))
    )
    (net (code "34") (name "LED_B0") (class "Default")
      (node (ref "B0") (pin "A") (pinfunction "A_A") (pintype "passive"))
      (node (ref "U2") (pin "69") (pinfunction "PA10_69") (pintype "bidirectional"))
    )
    (net (code "35") (name "LED_ERR") (class "Default")
      (node (ref "ERR") (pin "A") (pinfunction "A_A") (pintype "passive"))
      (node (ref "U2") (pin "70") (pinfunction "PA11_70") (pintype "bidirectional"))
    )
    (net (code "36") (name "LED_K_PI_BUTT") (class "Default")
      (node (ref "R10") (pin "1") (pinfunction "1_1") (pintype "passive"))
      (node (ref "SW_PANEL") (pin "5") (pinfunction "5_5") (pintype "passive"))
    )
    (net (code "37") (name "LOAD1") (class "Default")
      (node (ref "C32") (pin "+") (pinfunction "+_+") (pintype "passive"))
      (node (ref "C38") (pin "+") (pinfunction "+_+") (pintype "passive"))
      (node (ref "C47") (pin "1") (pinfunction "P$1_1") (pintype "passive"))
      (node (ref "C49") (pin "1") (pinfunction "P$1_1") (pintype "passive"))
      (node (ref "L3") (pin "P$1") (pinfunction "P$1_P$1") (pintype "bidirectional"))
      (node (ref "R23") (pin "2") (pinfunction "2_2") (pintype "passive"))
      (node (ref "RF") (pin "3") (pinfunction "3_3") (pintype "passive"))
      (node (ref "RM") (pin "3") (pinfunction "3_3") (pintype "passive"))
      (node (ref "RR") (pin "3") (pinfunction "3_3") (pintype "passive"))
    )
    (net (code "38") (name "LOAD2") (class "Default")
      (node (ref "C55") (pin "1") (pinfunction "P$1_1") (pintype "passive"))
      (node (ref "C56") (pin "1") (pinfunction "P$1_1") (pintype "passive"))
      (node (ref "C91") (pin "+") (pinfunction "+_+") (pintype "passive"))
      (node (ref "C92") (pin "+") (pinfunction "+_+") (pintype "passive"))
      (node (ref "L2") (pin "P$2") (pinfunction "P$2_P$2") (pintype "bidirectional"))
      (node (ref "LF") (pin "3") (pinfunction "3_3") (pintype "passive"))
      (node (ref "LM") (pin "3") (pinfunction "3_3") (pintype "passive"))
      (node (ref "LR") (pin "3") (pinfunction "3_3") (pintype "passive"))
      (node (ref "R21") (pin "2") (pinfunction "2_2") (pintype "passive"))
    )
    (net (code "39") (name "LTC4015_ALERT") (class "Default")
      (node (ref "LTC4015") (pin "6") (pinfunction "~{SMBALERT}_6") (pintype "bidirectional"))
      (node (ref "U2") (pin "18") (pinfunction "PC3_18") (pintype "bidirectional"))
    )
    (net (code "40") (name "MAIN_SWITCH") (class "Default")
      (node (ref "Q13") (pin "B") (pinfunction "B_B") (pintype "passive"))
      (node (ref "U2") (pin "57") (pinfunction "PD10_57") (pintype "bidirectional"))
    )
    (net (code "41") (name "Net-(5V-FB)") (class "Default")
      (node (ref "5V") (pin "5") (pinfunction "FB_5") (pintype "input"))
      (node (ref "RFBB") (pin "1") (pinfunction "1_1") (pintype "passive"))
      (node (ref "RFBT") (pin "1") (pinfunction "1_1") (pintype "passive"))
    )
    (net (code "42") (name "Net-(5V-SS{slash}TRK)") (class "Default")
      (node (ref "5V") (pin "6") (pinfunction "SS/TRK_6") (pintype "bidirectional"))
      (node (ref "C79") (pin "1") (pinfunction "P$1_1") (pintype "passive"))
    )
    (net (code "43") (name "Net-(ACT-PadC)") (class "Default")
      (node (ref "ACT") (pin "C") (pinfunction "C_C") (pintype "passive"))
      (node (ref "R4") (pin "1") (pinfunction "1_1") (pintype "passive"))
    )
    (net (code "44") (name "Net-(B0-PadC)") (class "Default")
      (node (ref "B0") (pin "C") (pinfunction "C_C") (pintype "passive"))
      (node (ref "R5") (pin "1") (pinfunction "1_1") (pintype "passive"))
    )
    (net (code "45") (name "Net-(C1-P$2)") (class "Default")
      (node (ref "C1") (pin "2") (pinfunction "P$2_2") (pintype "passive"))
      (node (ref "R31") (pin "2") (pinfunction "2_2") (pintype "passive"))
      (node (ref "RST") (pin "P$3") (pinfunction "P$3_P$3") (pintype "bidirectional"))
    )
    (net (code "46") (name "Net-(C3-P$1)") (class "Default")
      (node (ref "C3") (pin "1") (pinfunction "P$1_1") (pintype "passive"))
      (node (ref "D2") (pin "C") (pinfunction "C_C") (pintype "passive"))
      (node (ref "LTC4015") (pin "25") (pinfunction "BOOST_25") (pintype "bidirectional"))
    )
    (net (code "47") (name "Net-(C3-P$2)") (class "Default")
      (node (ref "C3") (pin "2") (pinfunction "P$2_2") (pintype "passive"))
      (node (ref "LTC4015") (pin "23") (pinfunction "SW_23") (pintype "bidirectional"))
      (node (ref "U3") (pin "4") (pinfunction "TGR_4") (pintype "passive"))
    )
    (net (code "48") (name "Net-(C4-P$2)") (class "Default")
      (node (ref "BATTERY") (pin "2") (pinfunction "2_2") (pintype "passive"))
      (node (ref "C4") (pin "2") (pinfunction "P$2_2") (pintype "passive"))
      (node (ref "C6") (pin "1") (pinfunction "P$1_1") (pintype "passive"))
      (node (ref "C7") (pin "1") (pinfunction "P$1_1") (pintype "passive"))
      (node (ref "LTC4015") (pin "18") (pinfunction "BATSENS_18") (pintype "input"))
      (node (ref "LTC4015") (pin "19") (pinfunction "CSN_19") (pintype "bidirectional"))
      (node (ref "RSNSB") (pin "1") (pinfunction "1_1") (pintype "passive"))
    )
    (net (code "49") (name "Net-(C5-P$1)") (class "Default")
      (node (ref "C5") (pin "1") (pinfunction "P$1_1") (pintype "passive"))
      (node (ref "LTC4015") (pin "15") (pinfunction "CSPM5_15") (pintype "bidirectional"))
    )
    (net (code "50") (name "Net-(C10-P$1)") (class "Default")
      (node (ref "C10") (pin "1") (pinfunction "P$1_1") (pintype "passive"))
      (node (ref "LTC4015") (pin "33") (pinfunction "CLP_33") (pintype "bidirectional"))
      (node (ref "M5") (pin "5") (pinfunction "D_5") (pintype "passive"))
      (node (ref "M5") (pin "6") (pinfunction "D_6") (pintype "passive"))
      (node (ref "M5") (pin "7") (pinfunction "D_7") (pintype "passive"))
      (node (ref "M5") (pin "8") (pinfunction "D_8") (pintype "passive"))
      (node (ref "RSNSI") (pin "2") (pinfunction "2_2") (pintype "passive"))
    )
    (net (code "51") (name "Net-(C11-P$2)") (class "Default")
      (node (ref "C11") (pin "2") (pinfunction "P$2_2") (pintype "passive"))
      (node (ref "LTC4015") (pin "30") (pinfunction "SYSM5_30") (pintype "input"))
    )
    (net (code "52") (name "Net-(C12-P$1)") (class "Default")
      (node (ref "C12") (pin "1") (pinfunction "P$1_1") (pintype "passive"))
      (node (ref "LTC4015") (pin "17") (pinfunction "CCREFP_17") (pintype "bidirectional"))
      (node (ref "RCCREF") (pin "1") (pinfunction "1_1") (pintype "passive"))
    )
    (net (code "53") (name "Net-(C12-P$2)") (class "Default")
      (node (ref "C12") (pin "2") (pinfunction "P$2_2") (pintype "passive"))
      (node (ref "LTC4015") (pin "16") (pinfunction "CCREFM_16") (pintype "bidirectional"))
      (node (ref "RCCREF") (pin "2") (pinfunction "2_2") (pintype "passive"))
    )
    (net (code "54") (name "Net-(C13-P$1)") (class "Default")
      (node (ref "C13") (pin "1") (pinfunction "P$1_1") (pintype "passive"))
      (node (ref "R12") (pin "1") (pinfunction "1_1") (pintype "passive"))
    )
    (net (code "55") (name "Net-(C14-P$1)") (class "Default")
      (node (ref "C14") (pin "1") (pinfunction "P$1_1") (pintype "passive"))
      (node (ref "LTC4015") (pin "9") (pinfunction "VC_9") (pintype "power_in"))
      (node (ref "R12") (pin "2") (pinfunction "2_2") (pintype "passive"))
    )
    (net (code "56") (name "Net-(C20-P$1)") (class "Default")
      (node (ref "C20") (pin "1") (pinfunction "P$1_1") (pintype "passive"))
      (node (ref "NTC1") (pin "8") (pinfunction "VCC_8") (pintype "power_in"))
      (node (ref "SJ2") (pin "2") (pinfunction "2_2") (pintype "passive"))
    )
    (net (code "57") (name "Net-(C29-P$1)") (class "Default")
      (node (ref "C29") (pin "1") (pinfunction "P$1_1") (pintype "passive"))
      (node (ref "NTC2") (pin "7") (pinfunction "A0_7") (pintype "bidirectional"))
      (node (ref "NTC2") (pin "8") (pinfunction "VCC_8") (pintype "power_in"))
      (node (ref "SJ3") (pin "2") (pinfunction "2_2") (pintype "passive"))
    )
    (net (code "58") (name "Net-(C30-P$1)") (class "Default")
      (node (ref "C30") (pin "1") (pinfunction "P$1_1") (pintype "passive"))
      (node (ref "D6") (pin "A") (pinfunction "A_A") (pintype "passive"))
      (node (ref "U$5") (pin "1") (pinfunction "VCC1_1") (pintype "passive"))
    )
    (net (code "59") (name "Net-(C31-P$1)") (class "Default")
      (node (ref "C31") (pin "1") (pinfunction "P$1_1") (pintype "passive"))
      (node (ref "D5") (pin "A") (pinfunction "A_A") (pintype "passive"))
      (node (ref "U$5") (pin "24") (pinfunction "VCC2_24") (pintype "passive"))
    )
    (net (code "60") (name "Net-(C33-P$2)") (class "Default")
      (node (ref "C33") (pin "2") (pinfunction "P$2_2") (pintype "passive"))
      (node (ref "U$5") (pin "18") (pinfunction "SS2_18") (pintype "passive"))
    )
    (net (code "61") (name "Net-(C34-P$2)") (class "Default")
      (node (ref "C34") (pin "2") (pinfunction "P$2_2") (pintype "passive"))
      (node (ref "U$5") (pin "14") (pinfunction "RES_14") (pintype "passive"))
    )
    (net (code "62") (name "Net-(C35-P$2)") (class "Default")
      (node (ref "C35") (pin "2") (pinfunction "P$2_2") (pintype "passive"))
      (node (ref "U$5") (pin "7") (pinfunction "SS1_7") (pintype "passive"))
    )
    (net (code "63") (name "Net-(C36-P$1)") (class "Default")
      (node (ref "C36") (pin "1") (pinfunction "P$1_1") (pintype "passive"))
      (node (ref "C37") (pin "1") (pinfunction "P$1_1") (pintype "passive"))
      (node (ref "R21") (pin "1") (pinfunction "1_1") (pintype "passive"))
      (node (ref "R22") (pin "2") (pinfunction "2_2") (pintype "passive"))
      (node (ref "U$5") (pin "16") (pinfunction "FB2_16") (pintype "passive"))
    )
    (net (code "64") (name "Net-(C36-P$2)") (class "Default")
      (node (ref "C36") (pin "2") (pinfunction "P$2_2") (pintype "passive"))
      (node (ref "R16") (pin "1") (pinfunction "1_1") (pintype "passive"))
    )
    (net (code "65") (name "Net-(C37-P$2)") (class "Default")
      (node (ref "C37") (pin "2") (pinfunction "P$2_2") (pintype "passive"))
      (node (ref "R16") (pin "2") (pinfunction "2_2") (pintype "passive"))
      (node (ref "U$5") (pin "15") (pinfunction "COMP2_15") (pintype "passive"))
    )
    (net (code "66") (name "Net-(C39-P$1)") (class "Default")
      (node (ref "C39") (pin "1") (pinfunction "P$1_1") (pintype "passive"))
      (node (ref "D5") (pin "C") (pinfunction "C_C") (pintype "passive"))
      (node (ref "U$5") (pin "27") (pinfunction "HB2_27") (pintype "passive"))
    )
    (net (code "67") (name "Net-(C39-P$2)") (class "Default")
      (node (ref "C39") (pin "2") (pinfunction "P$2_2") (pintype "passive"))
      (node (ref "U$5") (pin "25") (pinfunction "SW2_25") (pintype "passive"))
      (node (ref "U4") (pin "4") (pinfunction "TGR_4") (pintype "passive"))
    )
    (net (code "68") (name "Net-(C40-P$1)") (class "Default")
      (node (ref "C40") (pin "1") (pinfunction "P$1_1") (pintype "passive"))
      (node (ref "D6") (pin "C") (pinfunction "C_C") (pintype "passive"))
      (node (ref "U$5") (pin "30") (pinfunction "HB1_30") (pintype "passive"))
    )
    (net (code "69") (name "Net-(C40-P$2)") (class "Default")
      (node (ref "C40") (pin "2") (pinfunction "P$2_2") (pintype "passive"))
      (node (ref "U$5") (pin "32") (pinfunction "SW1_32") (pintype "passive"))
      (node (ref "U6") (pin "4") (pinfunction "TGR_4") (pintype "passive"))
    )
    (net (code "70") (name "Net-(C41-P$1)") (class "Default")
      (node (ref "C41") (pin "1") (pinfunction "P$1_1") (pintype "passive"))
      (node (ref "C42") (pin "1") (pinfunction "P$1_1") (pintype "passive"))
      (node (ref "R23") (pin "1") (pinfunction "1_1") (pintype "passive"))
      (node (ref "R24") (pin "2") (pinfunction "2_2") (pintype "passive"))
      (node (ref "U$5") (pin "9") (pinfunction "FB1_9") (pintype "passive"))
    )
    (net (code "71") (name "Net-(C41-P$2)") (class "Default")
      (node (ref "C41") (pin "2") (pinfunction "P$2_2") (pintype "passive"))
      (node (ref "R17") (pin "1") (pinfunction "1_1") (pintype "passive"))
    )
    (net (code "72") (name "Net-(C42-P$2)") (class "Default")
      (node (ref "C42") (pin "2") (pinfunction "P$2_2") (pintype "passive"))
      (node (ref "R17") (pin "2") (pinfunction "2_2") (pintype "passive"))
      (node (ref "U$5") (pin "10") (pinfunction "COMP1_10") (pintype "passive"))
    )
    (net (code "73") (name "Net-(C51-P$2)") (class "Default")
      (node (ref "C51") (pin "2") (pinfunction "P$2_2") (pintype "passive"))
      (node (ref "R19") (pin "1") (pinfunction "1_1") (pintype "passive"))
      (node (ref "U$5") (pin "6") (pinfunction "RAMP1_6") (pintype "passive"))
    )
    (net (code "74") (name "Net-(C52-P$1)") (class "Default")
      (node (ref "C52") (pin "1") (pinfunction "P$1_1") (pintype "passive"))
      (node (ref "R20") (pin "1") (pinfunction "1_1") (pintype "passive"))
      (node (ref "U$5") (pin "19") (pinfunction "RAMP2_19") (pintype "passive"))
    )
    (net (code "75") (name "Net-(C57-P$2)") (class "Default")
      (node (ref "C57") (pin "2") (pinfunction "P$2_2") (pintype "passive"))
      (node (ref "C58") (pin "2") (pinfunction "P$2_2") (pintype "passive"))
      (node (ref "C59") (pin "2") (pinfunction "P$2_2") (pintype "passive"))
      (node (ref "C60") (pin "2") (pinfunction "P$2_2") (pintype "passive"))
      (node (ref "C61") (pin "2") (pinfunction "P$2_2") (pintype "passive"))
      (node (ref "C62") (pin "2") (pinfunction "P$2_2") (pintype "passive"))
      (node (ref "C65") (pin "2") (pinfunction "P$2_2") (pintype "passive"))
      (node (ref "C66") (pin "2") (pinfunction "P$2_2") (pintype "passive"))
      (node (ref "FB1") (pin "1") (pinfunction "P$1_1") (pintype "passive"))
      (node (ref "FB2") (pin "1") (pinfunction "P$1_1") (pintype "passive"))
      (node (ref "U2") (pin "100") (pinfunction "VDD-2_100") (pintype "power_in"))
      (node (ref "U2") (pin "11") (pinfunction "VDD-3_11") (pintype "power_in"))
      (node (ref "U2") (pin "19") (pinfunction "VDD-4_19") (pintype "power_in"))
      (node (ref "U2") (pin "22") (pinfunction "VDDA_22") (pintype "power_in"))
      (node (ref "U2") (pin "28") (pinfunction "VDD-5_28") (pintype "power_in"))
      (node (ref "U2") (pin "50") (pinfunction "VDD-1_50") (pintype "power_in"))
      (node (ref "U2") (pin "6") (pinfunction "VBAT_6") (pintype "power_in"))
      (node (ref "U2") (pin "75") (pinfunction "VDD_75") (pintype "power_in"))
    )
    (net (code "76") (name "Net-(C63-P$1)") (class "Default")
      (node (ref "C63") (pin "1") (pinfunction "P$1_1") (pintype "passive"))
      (node (ref "C64") (pin "1") (pinfunction "P$1_1") (pintype "passive"))
      (node (ref "FB2") (pin "2") (pinfunction "P$2_2") (pintype "passive"))
      (node (ref "R25") (pin "2") (pinfunction "2_2") (pintype "passive"))
    )
    (net (code "77") (name "Net-(C67-P$1)") (class "Default")
      (node (ref "C67") (pin "1") (pinfunction "P$1_1") (pintype "passive"))
      (node (ref "U2") (pin "49") (pinfunction "VCAP_1_49") (pintype "power_in"))
    )
    (net (code "78") (name "Net-(C68-P$1)") (class "Default")
      (node (ref "C68") (pin "1") (pinfunction "P$1_1") (pintype "passive"))
      (node (ref "U2") (pin "73") (pinfunction "VCAP_2_73") (pintype "power_in"))
    )
    (net (code "79") (name "Net-(C72-P$1)") (class "Default")
      (node (ref "C72") (pin "1") (pinfunction "P$1_1") (pintype "passive"))
      (node (ref "D1") (pin "4") (pinfunction "K1K2_4") (pintype "passive"))
      (node (ref "IC1") (pin "3") (pinfunction "VIN_3") (pintype "input"))
    )
    (net (code "80") (name "Net-(C73-P$1)") (class "Default")
      (node (ref "C73") (pin "1") (pinfunction "P$1_1") (pintype "passive"))
      (node (ref "FAN") (pin "3") (pinfunction "3_3") (pintype "passive"))
      (node (ref "IC1") (pin "2") (pinfunction "VOUT_2") (pintype "output"))
    )
    (net (code "81") (name "Net-(C78-P$1)") (class "Default")
      (node (ref "C78") (pin "1") (pinfunction "P$1_1") (pintype "passive"))
      (node (ref "L5") (pin "1") (pinfunction "1_1") (pintype "passive"))
      (node (ref "U7") (pin "8") (pinfunction "+VOUT_8") (pintype "output"))
    )
    (net (code "82") (name "Net-(C88-P$2)") (class "Default")
      (node (ref "C88") (pin "2") (pinfunction "P$2_2") (pintype "passive"))
      (node (ref "C89") (pin "2") (pinfunction "P$2_2") (pintype "passive"))
      (node (ref "JPF1") (pin "P$2") (pinfunction "2_P$2") (pintype "passive"))
      (node (ref "U5") (pin "1") (pinfunction "VA_1") (pintype "bidirectional"))
    )
    (net (code "83") (name "Net-(C90-P$1)") (class "Default")
      (node (ref "C90") (pin "1") (pinfunction "P$1_1") (pintype "passive"))
      (node (ref "R32") (pin "1") (pinfunction "1_1") (pintype "passive"))
      (node (ref "U5") (pin "3") (pinfunction "VIN_3") (pintype "bidirectional"))
    )
    (net (code "84") (name "Net-(C94-P$1)") (class "Default")
      (node (ref "C94") (pin "1") (pinfunction "P$1_1") (pintype "passive"))
      (node (ref "C98") (pin "1") (pinfunction "P$1_1") (pintype "passive"))
      (node (ref "SJ1") (pin "2") (pinfunction "2_2") (pintype "passive"))
      (node (ref "U1") (pin "1") (pinfunction "VDDIO_1") (pintype "power_in"))
      (node (ref "U1") (pin "22") (pinfunction "VDD_22") (pintype "power_in"))
      (node (ref "U1") (pin "23") (pinfunction "VDD_23") (pintype "power_in"))
      (node (ref "U1") (pin "3") (pinfunction "VDDIO_3") (pintype "power_in"))
    )
    (net (code "85") (name "Net-(C96-P$1)") (class "Default")
      (node (ref "C96") (pin "1") (pinfunction "P$1_1") (pintype "passive"))
      (node (ref "U1") (pin "24") (pinfunction "C1_24") (pintype "passive"))
    )
    (net (code "86") (name "Net-(C97-P$1)") (class "Default")
      (node (ref "C97") (pin "1") (pinfunction "P$1_1") (pintype "passive"))
      (node (ref "U1") (pin "21") (pinfunction "CAP_21") (pintype "passive"))
    )
    (net (code "87") (name "Net-(D4-A2)") (class "Default")
      (node (ref "D4") (pin "2") (pinfunction "A2_2") (pintype "passive"))
      (node (ref "Q14") (pin "C") (pinfunction "C_C") (pintype "passive"))
    )
    (net (code "88") (name "Net-(D4-C)") (class "Default")
      (node (ref "3V3") (pin "EN") (pinfunction "EN_EN") (pintype "bidirectional"))
      (node (ref "D4") (pin "3") (pinfunction "C_3") (pintype "passive"))
      (node (ref "R44") (pin "1") (pinfunction "1_1") (pintype "passive"))
    )
    (net (code "89") (name "Net-(ERR-PadC)") (class "Default")
      (node (ref "ERR") (pin "C") (pinfunction "C_C") (pintype "passive"))
      (node (ref "R6") (pin "1") (pinfunction "1_1") (pintype "passive"))
    )
    (net (code "90") (name "Net-(JPF-2)") (class "Default")
      (node (ref "FLEX_OLED") (pin "1") (pinfunction "1_1") (pintype "passive"))
      (node (ref "JPF") (pin "P$2") (pinfunction "2_P$2") (pintype "passive"))
    )
    (net (code "91") (name "Net-(JTAG-Pad6)") (class "Default")
      (node (ref "JTAG") (pin "6") (pinfunction "6_6") (pintype "passive"))
      (node (ref "R1") (pin "1") (pinfunction "1_1") (pintype "passive"))
    )
    (net (code "92") (name "Net-(JTAG-Pad10)") (class "Default")
      (node (ref "JTAG") (pin "10") (pinfunction "10_10") (pintype "passive"))
      (node (ref "R2") (pin "1") (pinfunction "1_1") (pintype "passive"))
    )
    (net (code "93") (name "Net-(L1-PadP$1)") (class "Default")
      (node (ref "L1") (pin "P$1") (pinfunction "P$1_P$1") (pintype "bidirectional"))
      (node (ref "U3") (pin "6") (pinfunction "VSW_6") (pintype "passive"))
      (node (ref "U3") (pin "7") (pinfunction "VSW_7") (pintype "passive"))
      (node (ref "U3") (pin "8") (pinfunction "VSW_8") (pintype "passive"))
    )
    (net (code "94") (name "Net-(L2-PadP$1)") (class "Default")
      (node (ref "L2") (pin "P$1") (pinfunction "P$1_P$1") (pintype "bidirectional"))
      (node (ref "R20") (pin "2") (pinfunction "2_2") (pintype "passive"))
      (node (ref "U4") (pin "6") (pinfunction "VSW_6") (pintype "passive"))
      (node (ref "U4") (pin "7") (pinfunction "VSW_7") (pintype "passive"))
      (node (ref "U4") (pin "8") (pinfunction "VSW_8") (pintype "passive"))
    )
    (net (code "95") (name "Net-(L3-PadP$2)") (class "Default")
      (node (ref "L3") (pin "P$2") (pinfunction "P$2_P$2") (pintype "bidirectional"))
      (node (ref "R19") (pin "2") (pinfunction "2_2") (pintype "passive"))
      (node (ref "U6") (pin "6") (pinfunction "VSW_6") (pintype "passive"))
      (node (ref "U6") (pin "7") (pinfunction "VSW_7") (pintype "passive"))
      (node (ref "U6") (pin "8") (pinfunction "VSW_8") (pintype "passive"))
    )
    (net (code "96") (name "Net-(LTC4015-BG)") (class "Default")
      (node (ref "LTC4015") (pin "26") (pinfunction "BG_26") (pintype "bidirectional"))
      (node (ref "U3") (pin "5") (pinfunction "BG_5") (pintype "passive"))
    )
    (net (code "97") (name "Net-(LTC4015-CHEM0)") (class "Default")
      (node (ref "CHEM0") (pin "2") (pinfunction "2_2") (pintype "passive"))
      (node (ref "LTC4015") (pin "36") (pinfunction "CHEM0_36") (pintype "bidirectional"))
    )
    (net (code "98") (name "Net-(LTC4015-CHEM1)") (class "Default")
      (node (ref "CHEM1") (pin "2") (pinfunction "2_2") (pintype "passive"))
      (node (ref "LTC4015") (pin "37") (pinfunction "CHEM1_37") (pintype "bidirectional"))
    )
    (net (code "99") (name "Net-(LTC4015-INFET)") (class "Default")
      (node (ref "LTC4015") (pin "34") (pinfunction "INFET_34") (pintype "input"))
      (node (ref "M5") (pin "4") (pinfunction "G_4") (pintype "passive"))
    )
    (net (code "100") (name "Net-(LTC4015-NTC)") (class "Default")
      (node (ref "LTC4015") (pin "11") (pinfunction "NTC_11") (pintype "input"))
      (node (ref "NTCBIAS") (pin "1") (pinfunction "1_1") (pintype "passive"))
      (node (ref "RSERIES") (pin "2") (pinfunction "2_2") (pintype "passive"))
    )
    (net (code "101") (name "Net-(LTC4015-NTCBIAS)") (class "Default")
      (node (ref "LTC4015") (pin "12") (pinfunction "NTCBIAS_12") (pintype "output"))
      (node (ref "NTCBIAS") (pin "2") (pinfunction "2_2") (pintype "passive"))
    )
    (net (code "102") (name "Net-(LTC4015-OUTFET)") (class "Default")
      (node (ref "LTC4015") (pin "29") (pinfunction "OUTFET_29") (pintype "output"))
      (node (ref "M4") (pin "4") (pinfunction "GATE_4") (pintype "passive"))
    )
    (net (code "103") (name "Net-(LTC4015-RT)") (class "Default")
      (node (ref "LTC4015") (pin "10") (pinfunction "RT_10") (pintype "power_in"))
      (node (ref "RT") (pin "1") (pinfunction "1_1") (pintype "passive"))
    )
    (net (code "104") (name "Net-(LTC4015-TG)") (class "Default")
      (node (ref "LTC4015") (pin "24") (pinfunction "TG_24") (pintype "bidirectional"))
      (node (ref "U3") (pin "3") (pinfunction "TG_3") (pintype "passive"))
    )
    (net (code "105") (name "Net-(LTC4015-UVCLFB)") (class "Default")
      (node (ref "LTC4015") (pin "8") (pinfunction "UVCLFB_8") (pintype "bidirectional"))
      (node (ref "R13") (pin "1") (pinfunction "1_1") (pintype "passive"))
    )
    (net (code "106") (name "Net-(NRST-PadP$1)") (class "Default")
      (node (ref "NRST") (pin "P$1") (pinfunction "P$1_P$1") (pintype "bidirectional"))
      (node (ref "RST") (pin "P$4") (pinfunction "P$4_P$4") (pintype "bidirectional"))
    )
    (net (code "107") (name "Net-(NRST-PadP$2)") (class "Default")
      (node (ref "NRST") (pin "P$2") (pinfunction "P$2_P$2") (pintype "bidirectional"))
      (node (ref "RST") (pin "P$1") (pinfunction "P$1_P$1") (pintype "bidirectional"))
    )
    (net (code "108") (name "Net-(NTC-Pad2)") (class "Default")
      (node (ref "NTC") (pin "2") (pinfunction "2_2") (pintype "passive"))
      (node (ref "RPARALLEL") (pin "1") (pinfunction "1_1") (pintype "passive"))
      (node (ref "RSERIES") (pin "1") (pinfunction "1_1") (pintype "passive"))
    )
    (net (code "109") (name "Net-(Q1-D)") (class "Default")
      (node (ref "BUZZ") (pin "P") (pinfunction "P_P") (pintype "passive"))
      (node (ref "Q1") (pin "3") (pinfunction "D_3") (pintype "passive"))
    )
    (net (code "110") (name "Net-(Q1-G)") (class "Default")
      (node (ref "Q1") (pin "1") (pinfunction "G_1") (pintype "passive"))
      (node (ref "Q5") (pin "C") (pinfunction "C_C") (pintype "passive"))
      (node (ref "R36") (pin "2") (pinfunction "2_2") (pintype "passive"))
    )
    (net (code "111") (name "Net-(Q4-G)") (class "Default")
      (node (ref "Q3") (pin "C") (pinfunction "C_C") (pintype "passive"))
      (node (ref "Q4") (pin "1") (pinfunction "G_1") (pintype "passive"))
      (node (ref "R35") (pin "2") (pinfunction "2_2") (pintype "passive"))
    )
    (net (code "112") (name "Net-(Q6-PadC)") (class "Default")
      (node (ref "Q6") (pin "C") (pinfunction "C_C") (pintype "passive"))
      (node (ref "Q7") (pin "B") (pinfunction "B_B") (pintype "passive"))
    )
    (net (code "113") (name "Net-(Q8-G)") (class "Default")
      (node (ref "Q2") (pin "C") (pinfunction "C_C") (pintype "passive"))
      (node (ref "Q8") (pin "1") (pinfunction "G_1") (pintype "passive"))
      (node (ref "R34") (pin "2") (pinfunction "2_2") (pintype "passive"))
    )
    (net (code "114") (name "Net-(Q10-G)") (class "Default")
      (node (ref "Q10") (pin "1") (pinfunction "G_1") (pintype "passive"))
      (node (ref "Q9") (pin "C") (pinfunction "C_C") (pintype "passive"))
      (node (ref "R39") (pin "2") (pinfunction "2_2") (pintype "passive"))
    )
    (net (code "115") (name "Net-(Q12-G)") (class "Default")
      (node (ref "Q11") (pin "C") (pinfunction "C_C") (pintype "passive"))
      (node (ref "Q12") (pin "1") (pinfunction "G_1") (pintype "passive"))
      (node (ref "R40") (pin "2") (pinfunction "2_2") (pintype "passive"))
    )
    (net (code "116") (name "Net-(SDO_AG-2)") (class "Default")
      (node (ref "SDO_AG") (pin "P$2") (pinfunction "2_P$2") (pintype "passive"))
      (node (ref "U1") (pin "5") (pinfunction "SDO_A/G_5") (pintype "output"))
    )
    (net (code "117") (name "Net-(SDO_M-2)") (class "Default")
      (node (ref "SDO_M") (pin "P$2") (pinfunction "2_P$2") (pintype "passive"))
      (node (ref "U1") (pin "6") (pinfunction "SDO_M_6") (pintype "output"))
    )
    (net (code "118") (name "Net-(SW1-PadP$1)") (class "Default")
      (node (ref "SW1") (pin "P$1") (pinfunction "P$1_P$1") (pintype "bidirectional"))
      (node (ref "USER") (pin "P$4") (pinfunction "P$4_P$4") (pintype "bidirectional"))
    )
    (net (code "119") (name "Net-(SW1-PadP$2)") (class "Default")
      (node (ref "SW1") (pin "P$2") (pinfunction "P$2_P$2") (pintype "bidirectional"))
      (node (ref "USER") (pin "P$1") (pinfunction "P$1_P$1") (pintype "bidirectional"))
    )
    (net (code "120") (name "Net-(U$5-CS1)") (class "Default")
      (node (ref "RSNS1") (pin "2") (pinfunction "2_2") (pintype "passive"))
      (node (ref "U$5") (pin "5") (pinfunction "CS1_5") (pintype "passive"))
      (node (ref "U6") (pin "9") (pinfunction "PGND_9") (pintype "power_in"))
    )
    (net (code "121") (name "Net-(U$5-CS2)") (class "Default")
      (node (ref "RSNS2") (pin "2") (pinfunction "2_2") (pintype "passive"))
      (node (ref "U$5") (pin "20") (pinfunction "CS2_20") (pintype "passive"))
      (node (ref "U4") (pin "9") (pinfunction "PGND_9") (pintype "power_in"))
    )
    (net (code "122") (name "Net-(U$5-HO1)") (class "Default")
      (node (ref "U$5") (pin "31") (pinfunction "HO1_31") (pintype "passive"))
      (node (ref "U6") (pin "3") (pinfunction "TG_3") (pintype "passive"))
    )
    (net (code "123") (name "Net-(U$5-HO2)") (class "Default")
      (node (ref "U$5") (pin "26") (pinfunction "HO2_26") (pintype "passive"))
      (node (ref "U4") (pin "3") (pinfunction "TG_3") (pintype "passive"))
    )
    (net (code "124") (name "Net-(U$5-LO1)") (class "Default")
      (node (ref "U$5") (pin "2") (pinfunction "LO1_2") (pintype "passive"))
      (node (ref "U6") (pin "5") (pinfunction "BG_5") (pintype "passive"))
    )
    (net (code "125") (name "Net-(U$5-LO2)") (class "Default")
      (node (ref "U$5") (pin "23") (pinfunction "LO2_23") (pintype "passive"))
      (node (ref "U4") (pin "5") (pinfunction "BG_5") (pintype "passive"))
    )
    (net (code "126") (name "Net-(U$5-RT)") (class "Default")
      (node (ref "R15") (pin "2") (pinfunction "2_2") (pintype "passive"))
      (node (ref "U$5") (pin "13") (pinfunction "RT_13") (pintype "passive"))
    )
    (net (code "127") (name "Net-(U$11-D)") (class "Default")
      (node (ref "R41") (pin "2") (pinfunction "2_2") (pintype "passive"))
      (node (ref "U$11") (pin "4") (pinfunction "D_4") (pintype "passive"))
      (node (ref "U$12") (pin "4") (pinfunction "D_4") (pintype "passive"))
    )
    (net (code "128") (name "Net-(U$11-G)") (class "Default")
      (node (ref "Q13") (pin "C") (pinfunction "C_C") (pintype "passive"))
      (node (ref "R41") (pin "1") (pinfunction "1_1") (pintype "passive"))
      (node (ref "R42") (pin "1") (pinfunction "1_1") (pintype "passive"))
      (node (ref "U$11") (pin "1") (pinfunction "G_1") (pintype "passive"))
      (node (ref "U$12") (pin "1") (pinfunction "G_1") (pintype "passive"))
    )
    (net (code "129") (name "Net-(U2-BOOT0)") (class "Default")
      (node (ref "R3") (pin "2") (pinfunction "2_2") (pintype "passive"))
      (node (ref "U2") (pin "94") (pinfunction "BOOT0_94") (pintype "bidirectional"))
    )
    (net (code "130") (name "Net-(U2-NRST)") (class "Default")
      (node (ref "R30") (pin "2") (pinfunction "2_2") (pintype "passive"))
      (node (ref "U2") (pin "14") (pinfunction "NRST_14") (pintype "bidirectional"))
    )
    (net (code "131") (name "Net-(U2-PB4{slash}JTRST)") (class "Default")
      (node (ref "R29") (pin "2") (pinfunction "2_2") (pintype "passive"))
      (node (ref "U2") (pin "90") (pinfunction "PB4/JTRST_90") (pintype "bidirectional"))
    )
    (net (code "132") (name "Net-(U2-VREF+)") (class "Default")
      (node (ref "R25") (pin "1") (pinfunction "1_1") (pintype "passive"))
      (node (ref "U2") (pin "21") (pinfunction "VREF+_21") (pintype "power_in"))
    )
    (net (code "133") (name "PI_GPIO_A") (class "Default")
      (node (ref "RPI") (pin "P$6") (pinfunction "P$6_P$6") (pintype "bidirectional"))
      (node (ref "U2") (pin "40") (pinfunction "PE9_40") (pintype "bidirectional"))
    )
    (net (code "134") (name "PI_GPIO_B") (class "Default")
      (node (ref "RPI") (pin "P$8") (pinfunction "P$8_P$8") (pintype "bidirectional"))
      (node (ref "U2") (pin "39") (pinfunction "PE8_39") (pintype "bidirectional"))
    )
    (net (code "135") (name "PI_I2C_BUSY") (class "Default")
      (node (ref "RPI") (pin "P$9") (pinfunction "P$9_P$9") (pintype "bidirectional"))
      (node (ref "U2") (pin "38") (pinfunction "PE7_38") (pintype "bidirectional"))
    )
    (net (code "136") (name "PI_I2C_LINE") (class "Default")
      (node (ref "RPI") (pin "P$11") (pinfunction "P$11_P$11") (pintype "bidirectional"))
      (node (ref "U2") (pin "37") (pinfunction "PB2_37") (pintype "bidirectional"))
    )
    (net (code "137") (name "PI_I2C_SCL") (class "Default")
      (node (ref "PI_SDA") (pin "2") (pinfunction "2_2") (pintype "passive"))
      (node (ref "RPI") (pin "P$5") (pinfunction "P$5_P$5") (pintype "bidirectional"))
    )
    (net (code "138") (name "PI_I2C_SDA") (class "Default")
      (node (ref "PI_SCL") (pin "2") (pinfunction "2_2") (pintype "passive"))
      (node (ref "RPI") (pin "P$7") (pinfunction "P$7_P$7") (pintype "bidirectional"))
    )
    (net (code "139") (name "PI_PWR_ON_OFF") (class "Default")
      (node (ref "Q3") (pin "B") (pinfunction "B_B") (pintype "passive"))
      (node (ref "U2") (pin "43") (pinfunction "PE12_43") (pintype "bidirectional"))
    )
    (net (code "140") (name "PI_SIG_OFF") (class "Default")
      (node (ref "RPI") (pin "P$4") (pinfunction "P$4_P$4") (pintype "bidirectional"))
      (node (ref "U2") (pin "41") (pinfunction "PE10_41") (pintype "bidirectional"))
    )
    (net (code "141") (name "PI_SIG_ON") (class "Default")
      (node (ref "RPI") (pin "P$2") (pinfunction "P$2_P$2") (pintype "bidirectional"))
      (node (ref "U2") (pin "42") (pinfunction "PE11_42") (pintype "bidirectional"))
    )
    (net (code "142") (name "PI_SPI_CLK") (class "Default")
      (node (ref "RPI") (pin "P$17") (pinfunction "P$17_P$17") (pintype "bidirectional"))
      (node (ref "U2") (pin "30") (pinfunction "PA5_30") (pintype "bidirectional"))
    )
    (net (code "143") (name "PI_SPI_CS") (class "Default")
      (node (ref "RPI") (pin "P$19") (pinfunction "P$19_P$19") (pintype "bidirectional"))
      (node (ref "U2") (pin "29") (pinfunction "PA4_29") (pintype "bidirectional"))
    )
    (net (code "144") (name "PI_SPI_MISO") (class "Default")
      (node (ref "RPI") (pin "P$15") (pinfunction "P$15_P$15") (pintype "bidirectional"))
      (node (ref "U2") (pin "31") (pinfunction "PA6_31") (pintype "bidirectional"))
    )
    (net (code "145") (name "PI_SPI_MOSI") (class "Default")
      (node (ref "RPI") (pin "P$13") (pinfunction "P$13_P$13") (pintype "bidirectional"))
      (node (ref "U2") (pin "32") (pinfunction "PA7_32") (pintype "bidirectional"))
    )
    (net (code "146") (name "POWER_EARS") (class "Default")
      (node (ref "C54") (pin "1") (pinfunction "P$1_1") (pintype "passive"))
      (node (ref "C99") (pin "1") (pinfunction "P$1_1") (pintype "passive"))
      (node (ref "Q10") (pin "3") (pinfunction "D_3") (pintype "passive"))
      (node (ref "SERVOS") (pin "P$5") (pinfunction "P$5_P$5") (pintype "bidirectional"))
      (node (ref "SERVOS") (pin "P$8") (pinfunction "P$8_P$8") (pintype "bidirectional"))
    )
    (net (code "147") (name "POWER_HOOD") (class "Default")
      (node (ref "C82") (pin "1") (pinfunction "P$1_1") (pintype "passive"))
      (node (ref "C85") (pin "1") (pinfunction "P$1_1") (pintype "passive"))
      (node (ref "HOOD") (pin "5") (pinfunction "5_5") (pintype "passive"))
      (node (ref "Q12") (pin "3") (pinfunction "D_3") (pintype "passive"))
    )
    (net (code "148") (name "POWER_NECK") (class "Default")
      (node (ref "C53") (pin "1") (pinfunction "P$1_1") (pintype "passive"))
      (node (ref "C95") (pin "1") (pinfunction "P$1_1") (pintype "passive"))
      (node (ref "Q8") (pin "3") (pinfunction "D_3") (pintype "passive"))
      (node (ref "SERVOS") (pin "P$11") (pinfunction "P$11_P$11") (pintype "bidirectional"))
      (node (ref "SERVOS") (pin "P$2") (pinfunction "P$2_P$2") (pintype "bidirectional"))
    )
    (net (code "149") (name "PRE_SYSTEM") (class "Default")
      (node (ref "3V3") (pin "VIN") (pinfunction "VIN_VIN") (pintype "bidirectional"))
      (node (ref "C10") (pin "2") (pinfunction "P$2_2") (pintype "passive"))
      (node (ref "C11") (pin "1") (pinfunction "P$1_1") (pintype "passive"))
      (node (ref "C19") (pin "1") (pinfunction "P$1_1") (pintype "passive"))
      (node (ref "C21") (pin "1") (pinfunction "P$1_1") (pintype "passive"))
      (node (ref "C22") (pin "1") (pinfunction "P$1_1") (pintype "passive"))
      (node (ref "C23") (pin "1") (pinfunction "P$1_1") (pintype "passive"))
      (node (ref "C24") (pin "1") (pinfunction "P$1_1") (pintype "passive"))
      (node (ref "C25") (pin "1") (pinfunction "P$1_1") (pintype "passive"))
      (node (ref "C26") (pin "1") (pinfunction "P$1_1") (pintype "passive"))
      (node (ref "C74") (pin "1") (pinfunction "P$1_1") (pintype "passive"))
      (node (ref "C9") (pin "1") (pinfunction "P$1_1") (pintype "passive"))
      (node (ref "C9") (pin "2") (pinfunction "P$2_2") (pintype "passive"))
      (node (ref "D1") (pin "1") (pinfunction "A1_1") (pintype "passive"))
      (node (ref "LTC4015") (pin "31") (pinfunction "SYS_31") (pintype "input"))
      (node (ref "LTC4015") (pin "32") (pinfunction "CLN_32") (pintype "bidirectional"))
      (node (ref "M4") (pin "1") (pinfunction "2_SOURCE_1") (pintype "passive"))
      (node (ref "M4") (pin "2") (pinfunction "2_SOURCE_2") (pintype "passive"))
      (node (ref "M4") (pin "3") (pinfunction "2_SOURCE_3") (pintype "passive"))
      (node (ref "ON_OFF") (pin "P$2") (pinfunction "P$2_P$2") (pintype "bidirectional"))
      (node (ref "R42") (pin "2") (pinfunction "2_2") (pintype "passive"))
      (node (ref "RSNSI") (pin "1") (pinfunction "1_1") (pintype "passive"))
      (node (ref "U$11") (pin "3") (pinfunction "S_3") (pintype "passive"))
      (node (ref "U3") (pin "1") (pinfunction "VIN_1") (pintype "input"))
      (node (ref "U3") (pin "2") (pinfunction "VIN_2") (pintype "input"))
    )
    (net (code "150") (name "PSU_EN") (class "Default")
      (node (ref "R18") (pin "2") (pinfunction "2_2") (pintype "passive"))
      (node (ref "U$5") (pin "28") (pinfunction "UVLO_28") (pintype "passive"))
      (node (ref "U2") (pin "71") (pinfunction "PA12_71") (pintype "bidirectional"))
    )
    (net (code "151") (name "PWM_EAR_L") (class "Default")
      (node (ref "SERVOS") (pin "P$4") (pinfunction "P$4_P$4") (pintype "bidirectional"))
      (node (ref "U2") (pin "64") (pinfunction "PC7_64") (pintype "bidirectional"))
    )
    (net (code "152") (name "PWM_EAR_R") (class "Default")
      (node (ref "SERVOS") (pin "P$9") (pinfunction "P$9_P$9") (pintype "bidirectional"))
      (node (ref "U2") (pin "63") (pinfunction "PC6_63") (pintype "bidirectional"))
    )
    (net (code "153") (name "PWM_HOOD") (class "Default")
      (node (ref "HOOD") (pin "4") (pinfunction "4_4") (pintype "passive"))
      (node (ref "U2") (pin "62") (pinfunction "PD15_62") (pintype "bidirectional"))
    )
    (net (code "154") (name "REG_3V3_EN") (class "Default")
      (node (ref "Q14") (pin "B") (pinfunction "B_B") (pintype "passive"))
      (node (ref "U2") (pin "4") (pinfunction "PE5_4") (pintype "bidirectional"))
    )
    (net (code "155") (name "REG_5V_EN") (class "Default")
      (node (ref "5V") (pin "3") (pinfunction "EN_3") (pintype "input"))
      (node (ref "R43") (pin "1") (pinfunction "1_1") (pintype "passive"))
      (node (ref "U2") (pin "59") (pinfunction "PD12_59") (pintype "bidirectional"))
    )
    (net (code "156") (name "RPI_PWR") (class "Default")
      (node (ref "C86") (pin "1") (pinfunction "P$1_1") (pintype "passive"))
      (node (ref "Q4") (pin "3") (pinfunction "D_3") (pintype "passive"))
      (node (ref "RPI") (pin "P$14") (pinfunction "P$14_P$14") (pintype "bidirectional"))
      (node (ref "RPI") (pin "P$16") (pinfunction "P$16_P$16") (pintype "bidirectional"))
    )
    (net (code "157") (name "SCL") (class "Default")
      (node (ref "LTC4015") (pin "4") (pinfunction "SCL_4") (pintype "input"))
      (node (ref "NTC1") (pin "2") (pinfunction "SCL_2") (pintype "bidirectional"))
      (node (ref "NTC2") (pin "2") (pinfunction "SCL_2") (pintype "bidirectional"))
      (node (ref "PI_SCL") (pin "1") (pinfunction "1_1") (pintype "passive"))
      (node (ref "R7") (pin "2") (pinfunction "2_2") (pintype "passive"))
      (node (ref "U1") (pin "2") (pinfunction "SCL/SPC_2") (pintype "input"))
      (node (ref "U2") (pin "47") (pinfunction "PB10_47") (pintype "bidirectional"))
      (node (ref "U5") (pin "5") (pinfunction "SCL_5") (pintype "bidirectional"))
    )
    (net (code "158") (name "SDA") (class "Default")
      (node (ref "LTC4015") (pin "5") (pinfunction "SDA_5") (pintype "bidirectional"))
      (node (ref "NTC1") (pin "1") (pinfunction "SDA_1") (pintype "bidirectional"))
      (node (ref "NTC2") (pin "1") (pinfunction "SDA_1") (pintype "bidirectional"))
      (node (ref "PI_SDA") (pin "1") (pinfunction "1_1") (pintype "passive"))
      (node (ref "R27") (pin "1") (pinfunction "1_1") (pintype "passive"))
      (node (ref "U1") (pin "4") (pinfunction "SDA/SDI/SDO_4") (pintype "bidirectional"))
      (node (ref "U2") (pin "48") (pinfunction "PB11_48") (pintype "bidirectional"))
      (node (ref "U5") (pin "6") (pinfunction "SDA_6") (pintype "bidirectional"))
    )
    (net (code "159") (name "SERVOS_RX_RPI") (class "Default")
      (node (ref "RPI") (pin "P$3") (pinfunction "P$3_P$3") (pintype "bidirectional"))
      (node (ref "RX") (pin "3") (pinfunction "3_3") (pintype "passive"))
    )
    (net (code "160") (name "SERVOS_RX_STM") (class "Default")
      (node (ref "RX") (pin "1") (pinfunction "1_1") (pintype "passive"))
      (node (ref "U2") (pin "55") (pinfunction "PD8_55") (pintype "bidirectional"))
    )
    (net (code "161") (name "SERVOS_TX") (class "Default")
      (node (ref "LF") (pin "2") (pinfunction "2_2") (pintype "passive"))
      (node (ref "LM") (pin "2") (pinfunction "2_2") (pintype "passive"))
      (node (ref "LR") (pin "2") (pinfunction "2_2") (pintype "passive"))
      (node (ref "RF") (pin "2") (pinfunction "2_2") (pintype "passive"))
      (node (ref "RM") (pin "2") (pinfunction "2_2") (pintype "passive"))
      (node (ref "RR") (pin "2") (pinfunction "2_2") (pintype "passive"))
      (node (ref "TX") (pin "2") (pinfunction "2_2") (pintype "passive"))
    )
    (net (code "162") (name "SERVOS_TX_RPI") (class "Default")
      (node (ref "RPI") (pin "P$1") (pinfunction "P$1_P$1") (pintype "bidirectional"))
      (node (ref "TX") (pin "3") (pinfunction "3_3") (pintype "passive"))
    )
    (net (code "163") (name "SERVOS_TX_STM") (class "Default")
      (node (ref "TX") (pin "1") (pinfunction "1_1") (pintype "passive"))
      (node (ref "U2") (pin "56") (pinfunction "PD9_56") (pintype "bidirectional"))
    )
    (net (code "164") (name "SERVO_PWR_EARS") (class "Default")
      (node (ref "Q9") (pin "B") (pinfunction "B_B") (pintype "passive"))
      (node (ref "U2") (pin "1") (pinfunction "PE2_1") (pintype "bidirectional"))
    )
    (net (code "165") (name "SERVO_PWR_HOOD") (class "Default")
      (node (ref "Q11") (pin "B") (pinfunction "B_B") (pintype "passive"))
      (node (ref "U2") (pin "3") (pinfunction "PE4_3") (pintype "bidirectional"))
    )
    (net (code "166") (name "SERVO_PWR_NECK") (class "Default")
      (node (ref "Q2") (pin "B") (pinfunction "B_B") (pintype "passive"))
      (node (ref "U2") (pin "2") (pinfunction "PE3_2") (pintype "bidirectional"))
    )
    (net (code "167") (name "SERVO_RX") (class "Default")
      (node (ref "LF") (pin "1") (pinfunction "1_1") (pintype "passive"))
      (node (ref "LM") (pin "1") (pinfunction "1_1") (pintype "passive"))
      (node (ref "LR") (pin "1") (pinfunction "1_1") (pintype "passive"))
      (node (ref "RF") (pin "1") (pinfunction "1_1") (pintype "passive"))
      (node (ref "RM") (pin "1") (pinfunction "1_1") (pintype "passive"))
      (node (ref "RR") (pin "1") (pinfunction "1_1") (pintype "passive"))
      (node (ref "RX") (pin "2") (pinfunction "2_2") (pintype "passive"))
    )
    (net (code "168") (name "SIG_SYSTEM") (class "Default")
      (node (ref "Q7") (pin "C") (pinfunction "C_C") (pintype "passive"))
      (node (ref "R28") (pin "2") (pinfunction "2_2") (pintype "passive"))
      (node (ref "U2") (pin "34") (pinfunction "PC5_34") (pintype "bidirectional"))
    )
    (net (code "169") (name "STM_BUZZER") (class "Default")
      (node (ref "Q5") (pin "B") (pinfunction "B_B") (pintype "passive"))
      (node (ref "U2") (pin "25") (pinfunction "PA2_25") (pintype "bidirectional"))
    )
    (net (code "170") (name "STM_FAN") (class "Default")
      (node (ref "FAN") (pin "1") (pinfunction "1_1") (pintype "passive"))
      (node (ref "U2") (pin "24") (pinfunction "PA1_24") (pintype "bidirectional"))
    )
    (net (code "171") (name "SW_HOOD") (class "Default")
      (node (ref "R11") (pin "2") (pinfunction "2_2") (pintype "passive"))
      (node (ref "SW_PANEL") (pin "1") (pinfunction "1_1") (pintype "passive"))
      (node (ref "U2") (pin "46") (pinfunction "PE15_46") (pintype "bidirectional"))
    )
    (net (code "172") (name "SW_PI_BOOT") (class "Default")
      (node (ref "R9") (pin "2") (pinfunction "2_2") (pintype "passive"))
      (node (ref "SW_PANEL") (pin "3") (pinfunction "3_3") (pintype "passive"))
      (node (ref "U2") (pin "45") (pinfunction "PE14_45") (pintype "bidirectional"))
    )
    (net (code "173") (name "SW_USER") (class "Default")
      (node (ref "R8") (pin "2") (pinfunction "2_2") (pintype "passive"))
      (node (ref "U2") (pin "67") (pinfunction "PA8_67") (pintype "bidirectional"))
      (node (ref "USER") (pin "P$3") (pinfunction "P$3_P$3") (pintype "bidirectional"))
    )
    (net (code "174") (name "SYSTEM") (class "Default")
      (node (ref "5V") (pin "1") (pinfunction "VIN_1") (pintype "input"))
      (node (ref "C101") (pin "1") (pinfunction "P$1_1") (pintype "passive"))
      (node (ref "C43") (pin "+") (pinfunction "+_+") (pintype "passive"))
      (node (ref "C44") (pin "+") (pinfunction "+_+") (pintype "passive"))
      (node (ref "C45") (pin "+") (pinfunction "+_+") (pintype "passive"))
      (node (ref "C46") (pin "+") (pinfunction "+_+") (pintype "passive"))
      (node (ref "C48") (pin "1") (pinfunction "P$1_1") (pintype "passive"))
      (node (ref "C50") (pin "1") (pinfunction "P$1_1") (pintype "passive"))
      (node (ref "C80") (pin "1") (pinfunction "P$1_1") (pintype "passive"))
      (node (ref "U$12") (pin "3") (pinfunction "S_3") (pintype "passive"))
      (node (ref "U$5") (pin "29") (pinfunction "VIN_29") (pintype "passive"))
      (node (ref "U4") (pin "1") (pinfunction "VIN_1") (pintype "input"))
      (node (ref "U4") (pin "2") (pinfunction "VIN_2") (pintype "input"))
      (node (ref "U6") (pin "1") (pinfunction "VIN_1") (pintype "input"))
      (node (ref "U6") (pin "2") (pinfunction "VIN_2") (pintype "input"))
    )
    (net (code "175") (name "T-IR") (class "Default")
      (node (ref "R32") (pin "2") (pinfunction "2_2") (pintype "passive"))
      (node (ref "T-IR") (pin "3") (pinfunction "3_3") (pintype "passive"))
    )
    (net (code "176") (name "USART2_RX_BT") (class "Default")
      (node (ref "U2") (pin "87") (pinfunction "PD6_87") (pintype "bidirectional"))
    )
    (net (code "177") (name "USART2_TX_BT") (class "Default")
      (node (ref "U2") (pin "86") (pinfunction "PD5_86") (pintype "bidirectional"))
    )
    (net (code "178") (name "unconnected-(BT-ANATEST0-Pad3)") (class "Default")
      (node (ref "BT") (pin "3") (pinfunction "ANATEST0_3") (pintype "input"))
    )
    (net (code "179") (name "unconnected-(BT-EXT_LPCLK-Pad1)") (class "Default")
      (node (ref "BT") (pin "1") (pinfunction "EXT_LPCLK_1") (pintype "input"))
    )
    (net (code "180") (name "unconnected-(BT-GPIO2-Pad2)") (class "Default")
      (node (ref "BT") (pin "2") (pinfunction "GPIO2_2") (pintype "bidirectional"))
    )
    (net (code "181") (name "unconnected-(BT-SPI_IRQ-Pad4)") (class "Default")
      (node (ref "BT") (pin "4") (pinfunction "SPI_IRQ_4") (pintype "output"))
    )
    (net (code "182") (name "unconnected-(JTAG-Pad7)") (class "Default")
      (node (ref "JTAG") (pin "7") (pinfunction "7_7") (pintype "passive"))
    )
    (net (code "183") (name "unconnected-(JTAG-Pad9)") (class "Default")
      (node (ref "JTAG") (pin "9") (pinfunction "9_9") (pintype "passive"))
    )
    (net (code "184") (name "unconnected-(NTC1-OS-Pad3)") (class "Default")
      (node (ref "NTC1") (pin "3") (pinfunction "OS_3") (pintype "bidirectional"))
    )
    (net (code "185") (name "unconnected-(NTC2-OS-Pad3)") (class "Default")
      (node (ref "NTC2") (pin "3") (pinfunction "OS_3") (pintype "bidirectional"))
    )
    (net (code "186") (name "unconnected-(U$5-DEMB-Pad17)") (class "Default")
      (node (ref "U$5") (pin "17") (pinfunction "DEMB_17") (pintype "passive"))
    )
    (net (code "187") (name "unconnected-(U$5-EN2-Pad11)") (class "Default")
      (node (ref "U$5") (pin "11") (pinfunction "EN2_11") (pintype "passive"))
    )
    (net (code "188") (name "unconnected-(U$5-EP_2-Pad12)") (class "Default")
      (node (ref "U$5") (pin "12") (pinfunction "EP_2_12") (pintype "passive"))
    )
    (net (code "189") (name "unconnected-(U$5-VCCDIS-Pad8)") (class "Default")
      (node (ref "U$5") (pin "8") (pinfunction "VCCDIS_8") (pintype "passive"))
    )
    (net (code "190") (name "unconnected-(U1-DEN_A{slash}G-Pad13)") (class "Default")
      (node (ref "U1") (pin "13") (pinfunction "DEN_A/G_13") (pintype "input"))
    )
    (net (code "191") (name "unconnected-(U1-DRDY_M-Pad9)") (class "Default")
      (node (ref "U1") (pin "9") (pinfunction "DRDY_M_9") (pintype "output"))
    )
    (net (code "192") (name "unconnected-(U1-INT1_A{slash}G-Pad11)") (class "Default")
      (node (ref "U1") (pin "11") (pinfunction "INT1_A/G_11") (pintype "output"))
    )
    (net (code "193") (name "unconnected-(U1-INT2_A{slash}G-Pad12)") (class "Default")
      (node (ref "U1") (pin "12") (pinfunction "INT2_A/G_12") (pintype "output"))
    )
    (net (code "194") (name "unconnected-(U1-INT_M-Pad10)") (class "Default")
      (node (ref "U1") (pin "10") (pinfunction "INT_M_10") (pintype "output"))
    )
    (net (code "195") (name "unconnected-(U2-PA0-Pad23)") (class "Default")
      (node (ref "U2") (pin "23") (pinfunction "PA0_23") (pintype "bidirectional"))
    )
    (net (code "196") (name "unconnected-(U2-PA3-Pad26)") (class "Default")
      (node (ref "U2") (pin "26") (pinfunction "PA3_26") (pintype "bidirectional"))
    )
    (net (code "197") (name "unconnected-(U2-PB0-Pad35)") (class "Default")
      (node (ref "U2") (pin "35") (pinfunction "PB0_35") (pintype "bidirectional"))
    )
    (net (code "198") (name "unconnected-(U2-PB1-Pad36)") (class "Default")
      (node (ref "U2") (pin "36") (pinfunction "PB1_36") (pintype "bidirectional"))
    )
    (net (code "199") (name "unconnected-(U2-PB5-Pad91)") (class "Default")
      (node (ref "U2") (pin "91") (pinfunction "PB5_91") (pintype "bidirectional"))
    )
    (net (code "200") (name "unconnected-(U2-PB8-Pad95)") (class "Default")
      (node (ref "U2") (pin "95") (pinfunction "PB8_95") (pintype "bidirectional"))
    )
    (net (code "201") (name "unconnected-(U2-PB9-Pad96)") (class "Default")
      (node (ref "U2") (pin "96") (pinfunction "PB9_96") (pintype "bidirectional"))
    )
    (net (code "202") (name "unconnected-(U2-PC0-Pad15)") (class "Default")
      (node (ref "U2") (pin "15") (pinfunction "PC0_15") (pintype "bidirectional"))
    )
    (net (code "203") (name "unconnected-(U2-PC1-Pad16)") (class "Default")
      (node (ref "U2") (pin "16") (pinfunction "PC1_16") (pintype "bidirectional"))
    )
    (net (code "204") (name "unconnected-(U2-PC2-Pad17)") (class "Default")
      (node (ref "U2") (pin "17") (pinfunction "PC2_17") (pintype "bidirectional"))
    )
    (net (code "205") (name "unconnected-(U2-PC4-Pad33)") (class "Default")
      (node (ref "U2") (pin "33") (pinfunction "PC4_33") (pintype "bidirectional"))
    )
    (net (code "206") (name "unconnected-(U2-PC13-Pad7)") (class "Default")
      (node (ref "U2") (pin "7") (pinfunction "PC13_7") (pintype "bidirectional"))
    )
    (net (code "207") (name "unconnected-(U2-PC14-Pad8)") (class "Default")
      (node (ref "U2") (pin "8") (pinfunction "PC14_8") (pintype "bidirectional"))
    )
    (net (code "208") (name "unconnected-(U2-PC15-Pad9)") (class "Default")
      (node (ref "U2") (pin "9") (pinfunction "PC15_9") (pintype "bidirectional"))
    )
    (net (code "209") (name "unconnected-(U2-PD3-Pad84)") (class "Default")
      (node (ref "U2") (pin "84") (pinfunction "PD3_84") (pintype "bidirectional"))
    )
    (net (code "210") (name "unconnected-(U2-PD4-Pad85)") (class "Default")
      (node (ref "U2") (pin "85") (pinfunction "PD4_85") (pintype "bidirectional"))
    )
    (net (code "211") (name "unconnected-(U2-PD7-Pad88)") (class "Default")
      (node (ref "U2") (pin "88") (pinfunction "PD7_88") (pintype "bidirectional"))
    )
    (net (code "212") (name "unconnected-(U2-PE0-Pad97)") (class "Default")
      (node (ref "U2") (pin "97") (pinfunction "PE0_97") (pintype "bidirectional"))
    )
    (net (code "213") (name "unconnected-(U2-PE1-Pad98)") (class "Default")
      (node (ref "U2") (pin "98") (pinfunction "PE1_98") (pintype "bidirectional"))
    )
    (net (code "214") (name "unconnected-(U2-PE6-Pad5)") (class "Default")
      (node (ref "U2") (pin "5") (pinfunction "PE6_5") (pintype "bidirectional"))
    )
    (net (code "215") (name "unconnected-(U2-PH0-Pad12)") (class "Default")
      (node (ref "U2") (pin "12") (pinfunction "PH0_12") (pintype "bidirectional"))
    )
    (net (code "216") (name "unconnected-(U2-PH1-Pad13)") (class "Default")
      (node (ref "U2") (pin "13") (pinfunction "PH1_13") (pintype "bidirectional"))
    )
    (net (code "217") (name "unconnected-(U5-ALERT-Pad4)") (class "Default")
      (node (ref "U5") (pin "4") (pinfunction "ALERT_4") (pintype "bidirectional"))
    )
    (net (code "218") (name "unconnected-(U7-NC-Pad14)") (class "Default")
      (node (ref "U7") (pin "14") (pinfunction "NC_14") (pintype "bidirectional"))
    )
  )
)
